# Schematic.net
KiCad netlist of a schematic drawn in EAGLE
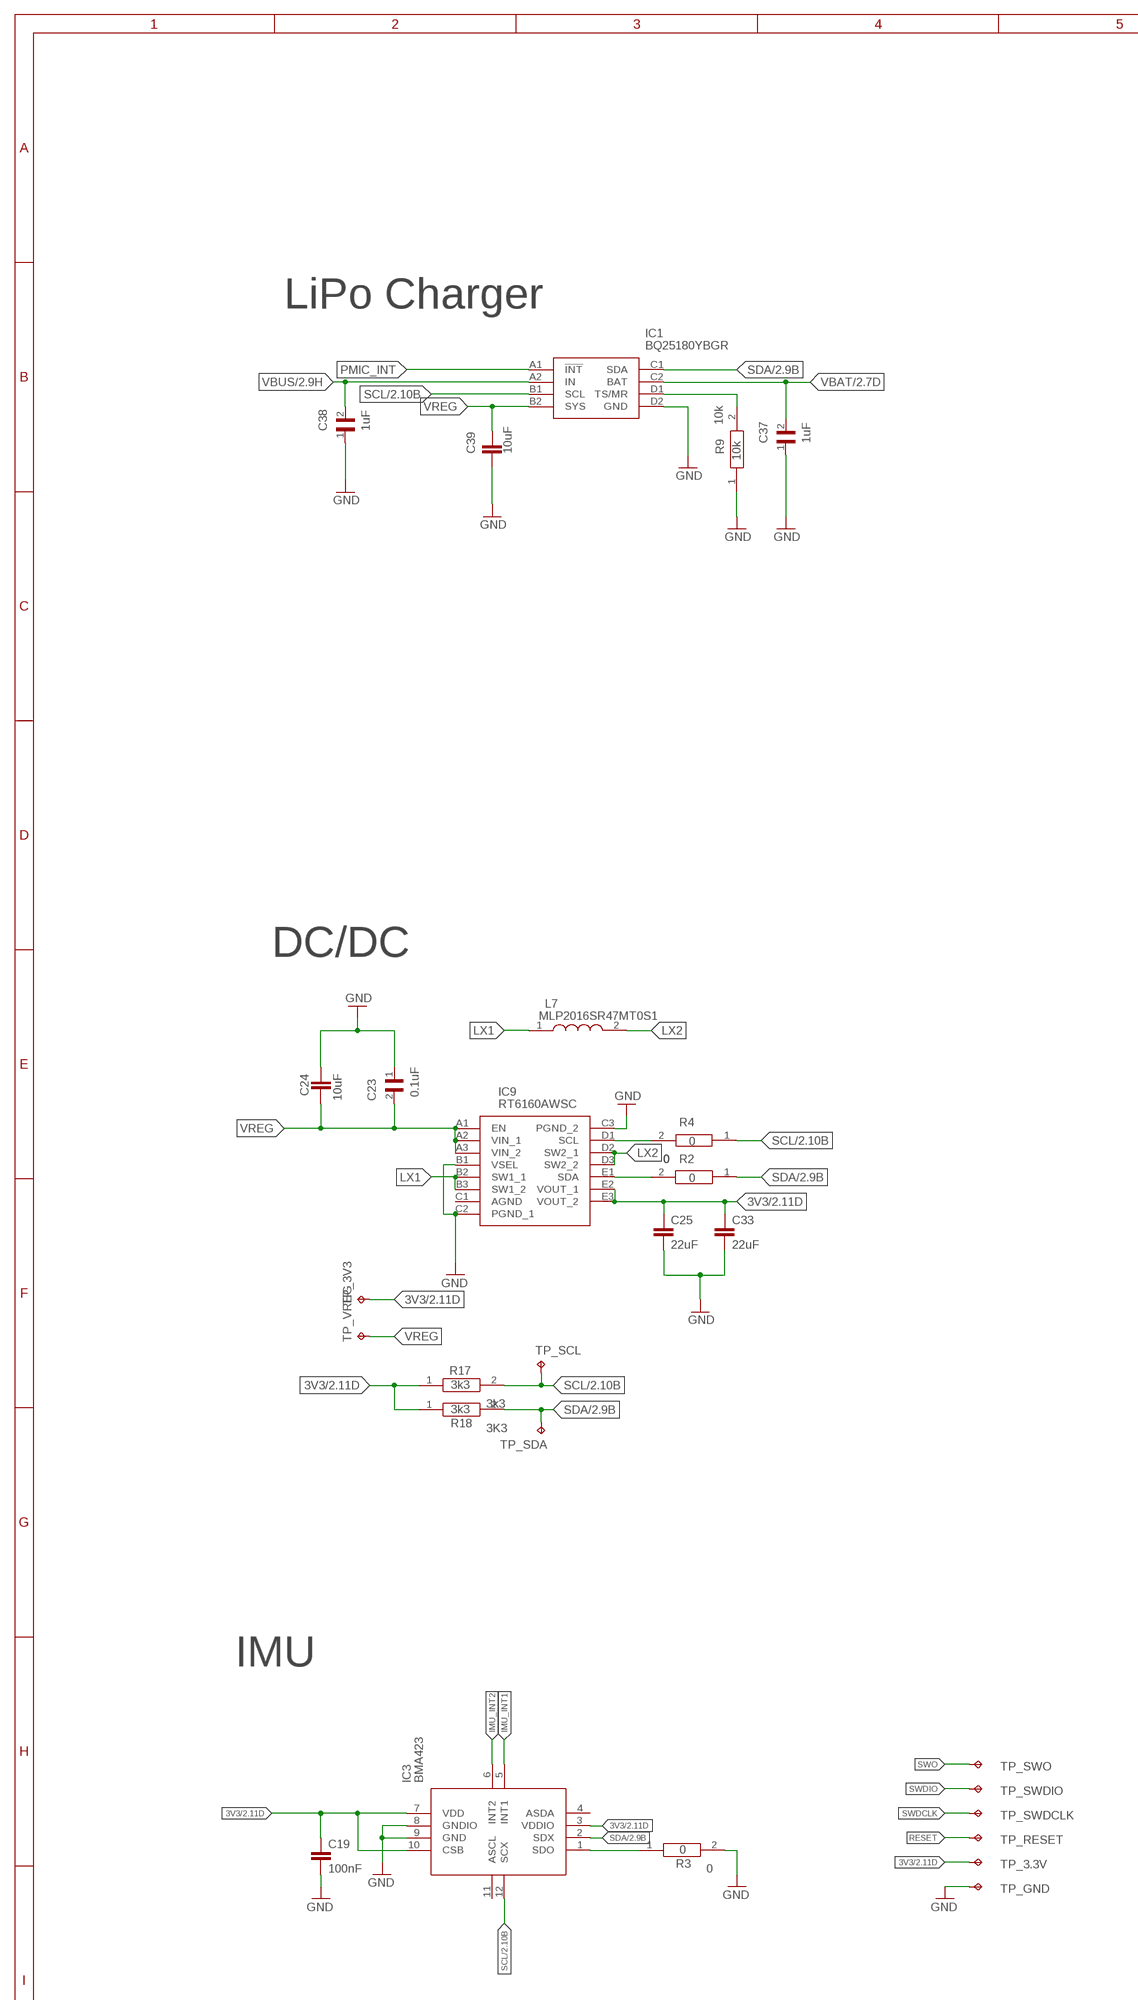
[diagram p0: schematic, sheet 1, part 1 of 2]
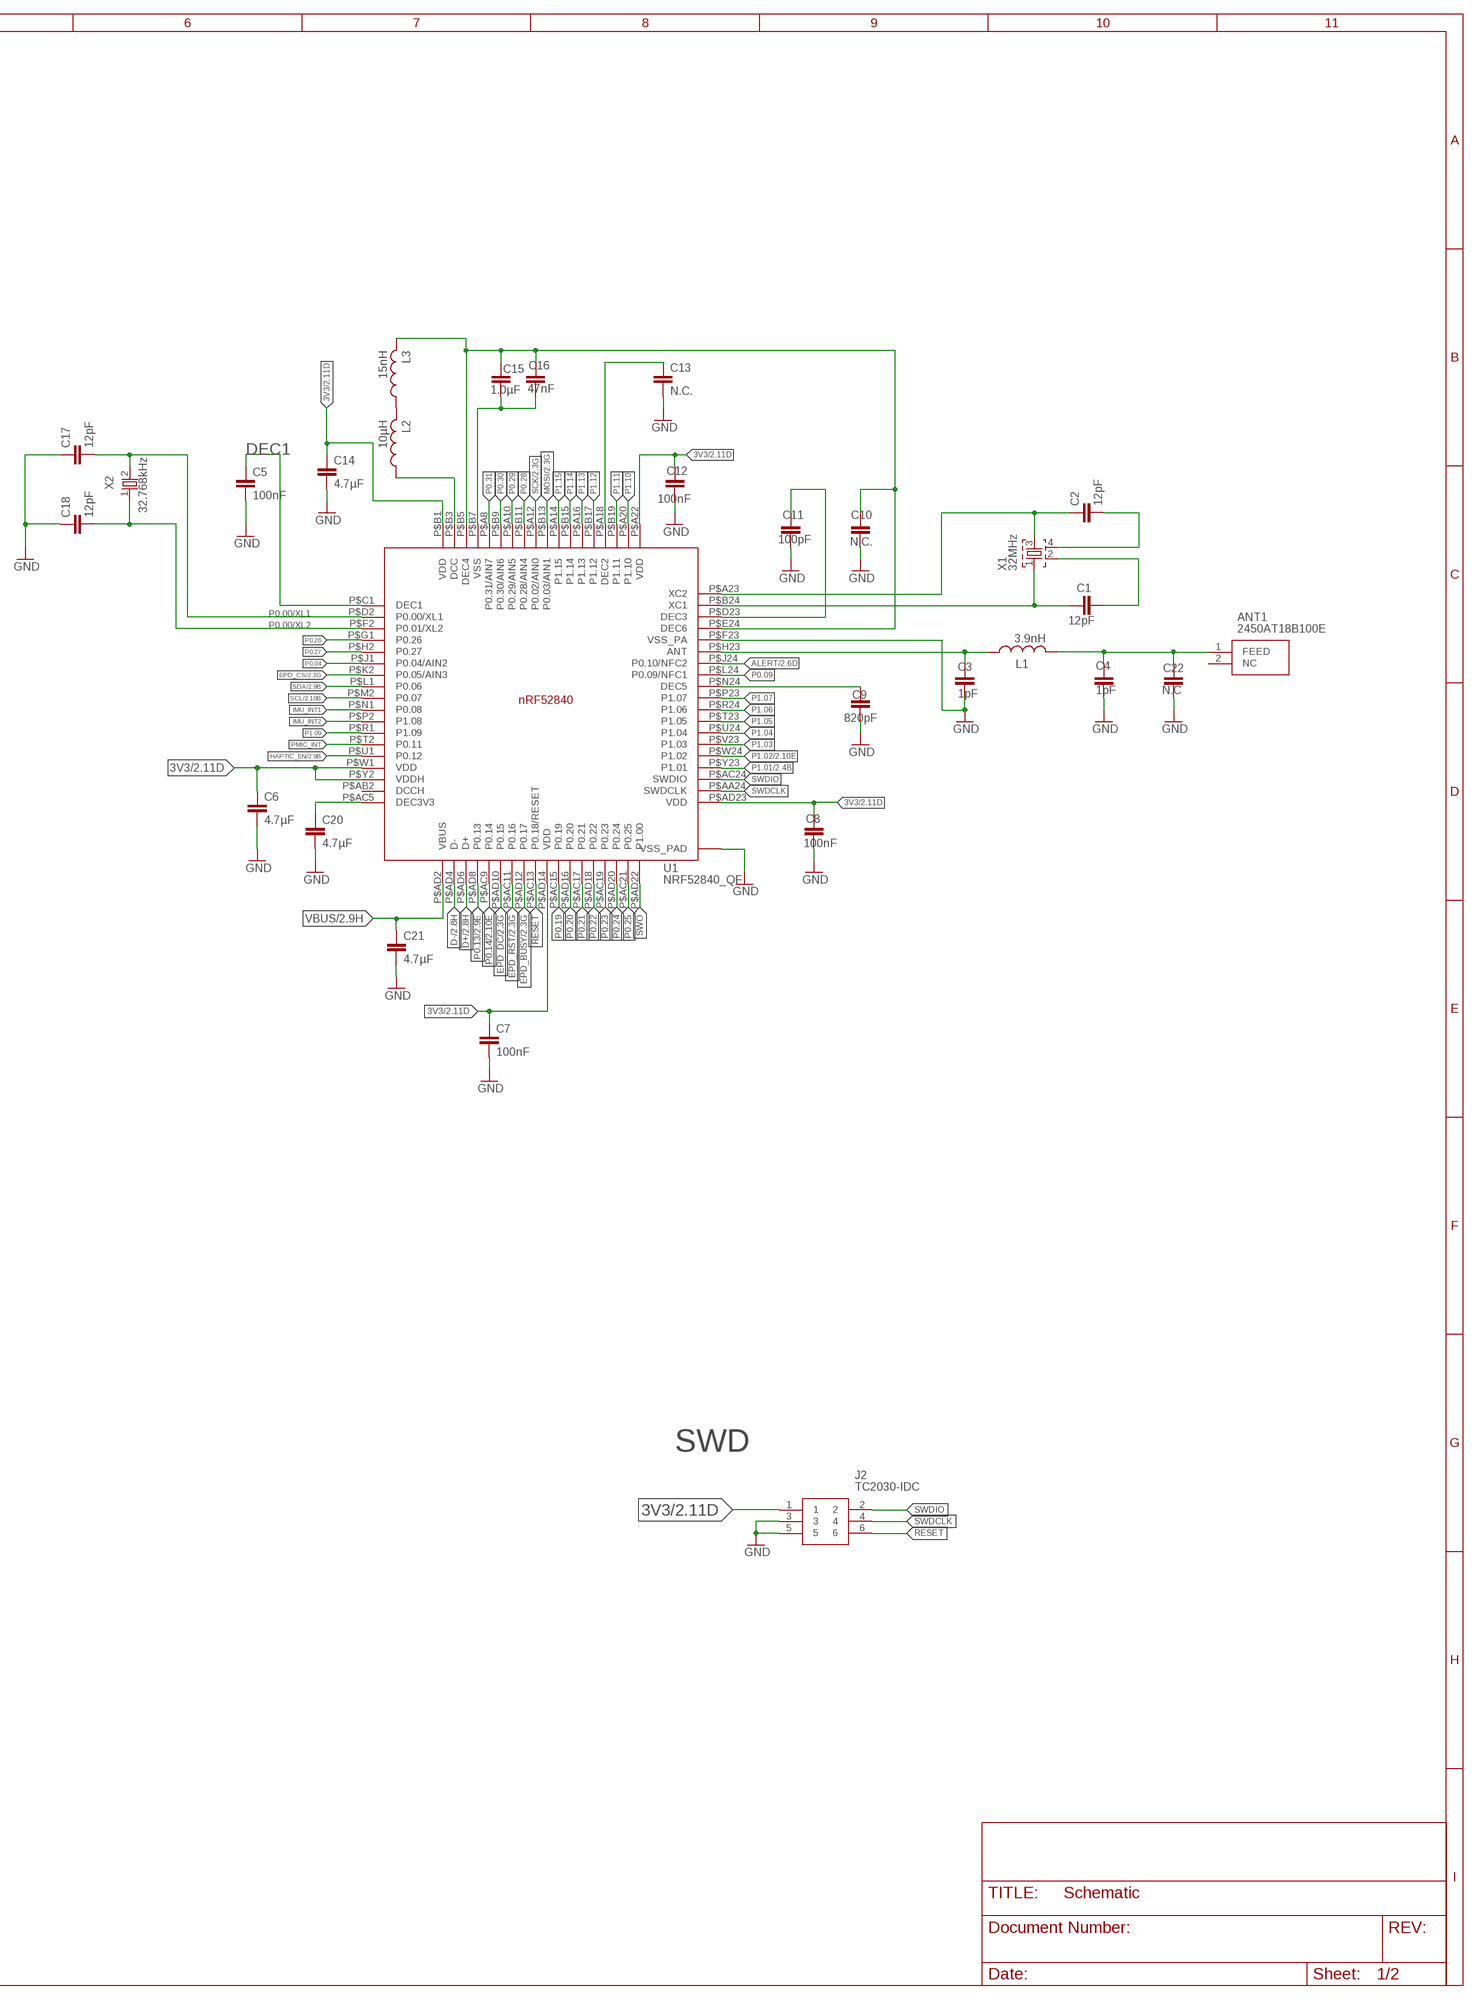
[diagram p1: schematic, sheet 1, part 2 of 2]
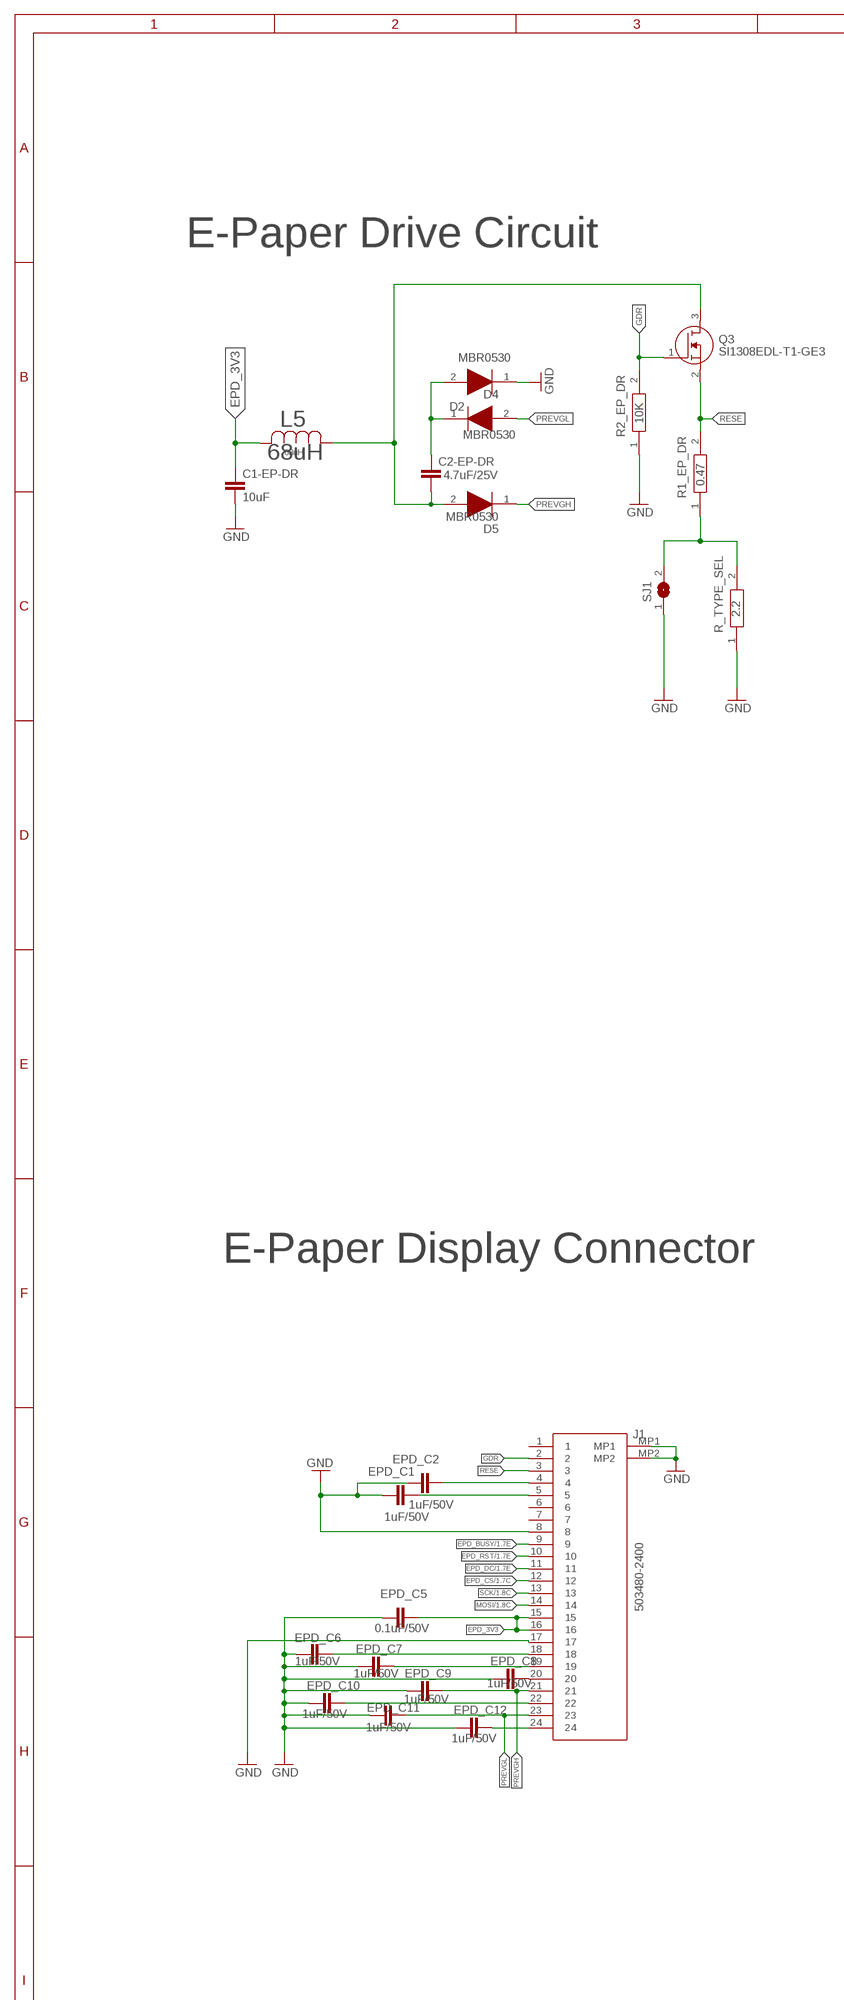
[diagram p2: schematic, sheet 2, part 1 of 2]
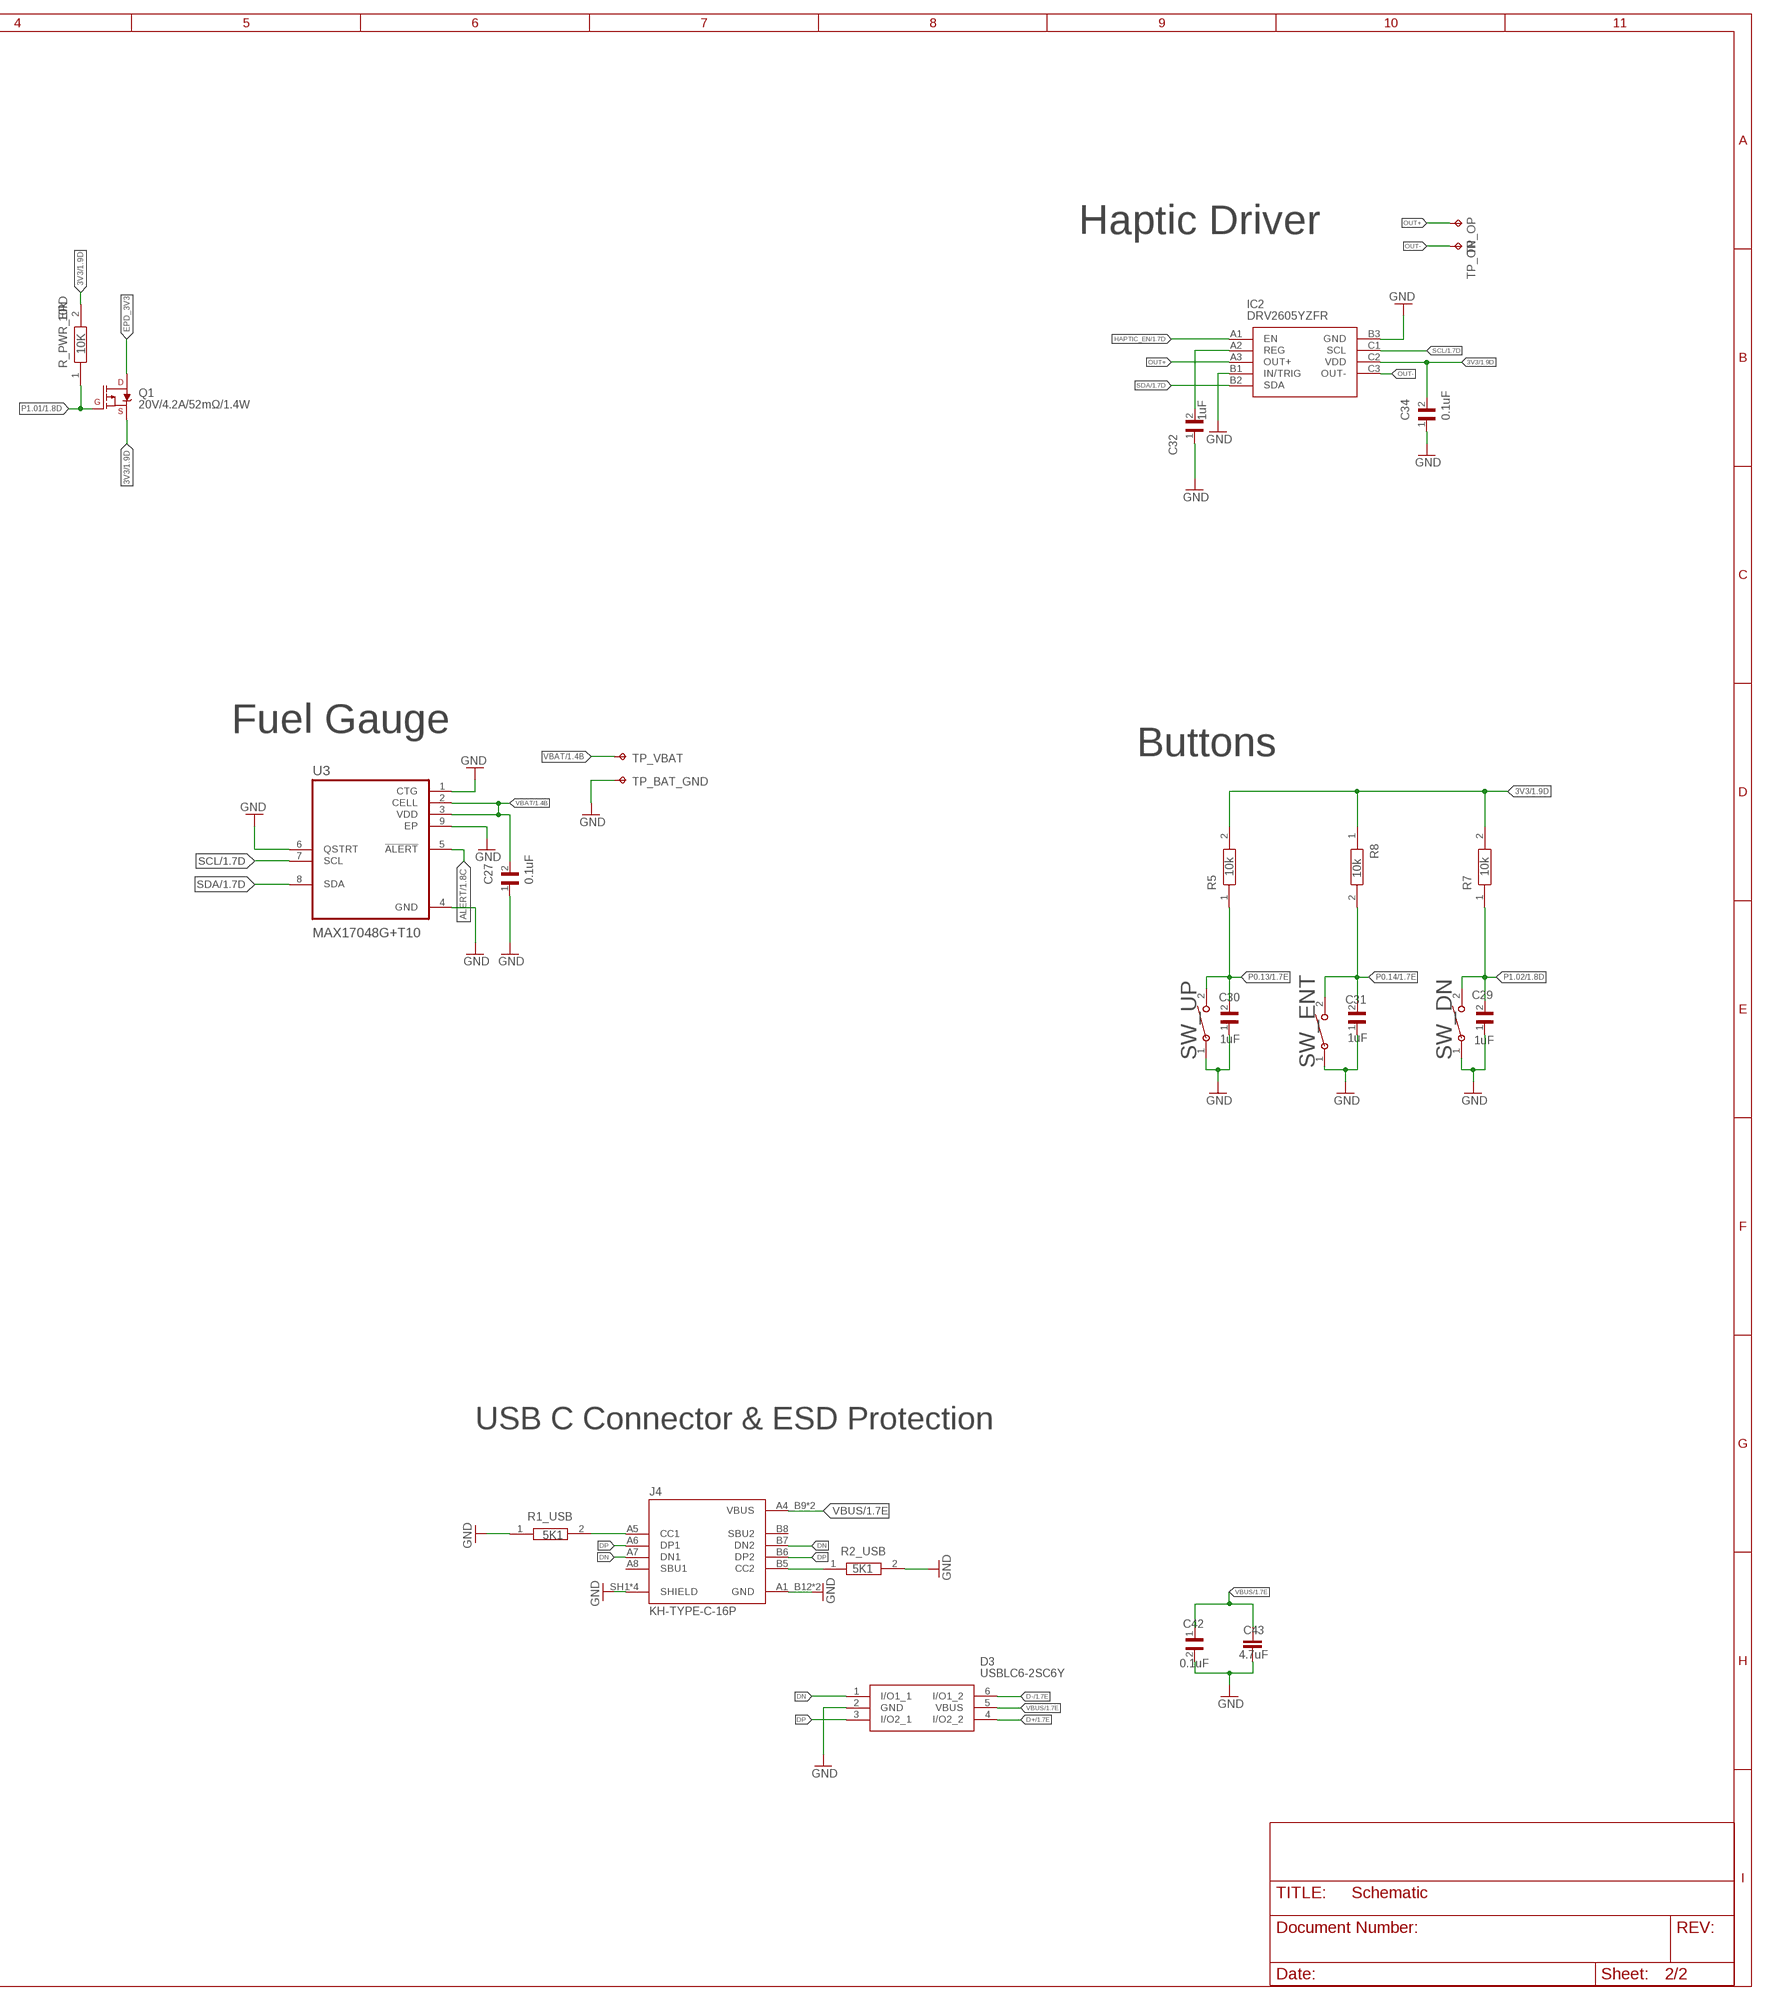
[diagram p3: schematic, sheet 2, part 2 of 2]

(export (version "E")
  (design (tool "Eeschema 10.0.6"))
  (components
    (comp (ref "C1-EP-DR")
      (value "10uF")
      (footprint "eagle-import:NORDIC_NRF_3_RESC0402_L")
      (libsource (lib "eagle-import") (part "InkTime_v5_vf.tUwrbmbJTRevvyDZ4HcNKA_NORDIC_NRF_3_CAPACITOR_0402_L"))
    )
    (comp (ref "C2-EP-DR")
      (value "4.7uF/25V")
      (footprint "eagle-import:NORDIC_NRF_3_RESC0402_L")
      (libsource (lib "eagle-import") (part "InkTime_v5_vf.tUwrbmbJTRevvyDZ4HcNKA_NORDIC_NRF_3_CAPACITOR_0402_L"))
    )
    (comp (ref "C27")
      (value "0.1uF")
      (footprint "eagle-import:GRM011R60J152KE01L_2_CAPC0201X13N")
      (fields (field (name "MF") "Murata") (field (name "MP") "GRM011R60J152KE01L"))
      (libsource (lib "eagle-import") (part "GRM011R60J152KE01L_2_GRM011R60J152KE01L"))
    )
    (comp (ref "C29")
      (value "1uF")
      (footprint "eagle-import:GRM011R60J152KE01L_2_CAPC0201X13N")
      (fields (field (name "MF") "Murata") (field (name "MP") "GRM011R60J152KE01L"))
      (libsource (lib "eagle-import") (part "GRM011R60J152KE01L_2_GRM011R60J152KE01L"))
    )
    (comp (ref "C30")
      (value "1uF")
      (footprint "eagle-import:GRM011R60J152KE01L_2_CAPC0201X13N")
      (fields (field (name "MF") "Murata") (field (name "MP") "GRM011R60J152KE01L"))
      (libsource (lib "eagle-import") (part "GRM011R60J152KE01L_2_GRM011R60J152KE01L"))
    )
    (comp (ref "C31")
      (value "1uF")
      (footprint "eagle-import:GRM011R60J152KE01L_2_CAPC0201X13N")
      (fields (field (name "MF") "Murata") (field (name "MP") "GRM011R60J152KE01L"))
      (libsource (lib "eagle-import") (part "GRM011R60J152KE01L_2_GRM011R60J152KE01L"))
    )
    (comp (ref "C32")
      (value "1uF")
      (footprint "eagle-import:GRM011R60J152KE01L_2_CAPC0201X13N")
      (fields (field (name "MF") "Murata") (field (name "MP") "GRM011R60J152KE01L"))
      (libsource (lib "eagle-import") (part "GRM011R60J152KE01L_2_GRM011R60J152KE01L"))
    )
    (comp (ref "C34")
      (value "0.1uF")
      (footprint "eagle-import:GRM011R60J152KE01L_2_CAPC0201X13N")
      (fields (field (name "MF") "Murata") (field (name "MP") "GRM011R60J152KE01L"))
      (libsource (lib "eagle-import") (part "GRM011R60J152KE01L_2_GRM011R60J152KE01L"))
    )
    (comp (ref "C42")
      (value "0.1uF")
      (footprint "eagle-import:GRM011R60J152KE01L_2_CAPC0201X13N")
      (fields (field (name "MF") "Murata") (field (name "MP") "GRM011R60J152KE01L"))
      (libsource (lib "eagle-import") (part "GRM011R60J152KE01L_2_GRM011R60J152KE01L"))
    )
    (comp (ref "C43")
      (value "4.7uF")
      (footprint "eagle-import:NORDIC_NRF_3_RESC0402_L")
      (libsource (lib "eagle-import") (part "InkTime_v5_vf.tUwrbmbJTRevvyDZ4HcNKA_NORDIC_NRF_3_CAPACITOR_0402_L"))
    )
    (comp (ref "D2")
      (value "MBR0530")
      (footprint "eagle-import:ESP32_C6_LIBRARY_5_SOD3716X135N")
      (fields (field (name "MF") "ON Semiconductor"))
      (libsource (lib "eagle-import") (part "ESP32_C6_LIBRARY_5_MBR0530"))
    )
    (comp (ref "D3")
      (value "USBLC6-2SC6Y")
      (footprint "eagle-import:ESP32_C6_LIBRARY_3_SOT95P280X145-6N")
      (fields (field (name "MF") "STMicroelectronics"))
      (libsource (lib "eagle-import") (part "ESP32_C6_LIBRARY_3_USBLC6-2SC6Y"))
    )
    (comp (ref "D4")
      (value "MBR0530")
      (footprint "eagle-import:ESP32_C6_LIBRARY_5_SOD3716X135N")
      (fields (field (name "MF") "ON Semiconductor"))
      (libsource (lib "eagle-import") (part "ESP32_C6_LIBRARY_5_MBR0530"))
    )
    (comp (ref "D5")
      (value "MBR0530")
      (footprint "eagle-import:ESP32_C6_LIBRARY_5_SOD3716X135N")
      (fields (field (name "MF") "ON Semiconductor"))
      (libsource (lib "eagle-import") (part "ESP32_C6_LIBRARY_5_MBR0530"))
    )
    (comp (ref "EPD_C1")
      (value "1uF/50V")
      (footprint "eagle-import:NORDIC_NRF_3_RESC0402_L")
      (libsource (lib "eagle-import") (part "InkTime_v5_vf.tUwrbmbJTRevvyDZ4HcNKA_NORDIC_NRF_3_CAPACITOR_0402_L"))
    )
    (comp (ref "EPD_C2")
      (value "1uF/50V")
      (footprint "eagle-import:NORDIC_NRF_3_RESC0402_L")
      (libsource (lib "eagle-import") (part "InkTime_v5_vf.tUwrbmbJTRevvyDZ4HcNKA_NORDIC_NRF_3_CAPACITOR_0402_L"))
    )
    (comp (ref "EPD_C5")
      (value "0.1uF/50V")
      (footprint "eagle-import:NORDIC_NRF_3_RESC0402_L")
      (libsource (lib "eagle-import") (part "InkTime_v5_vf.tUwrbmbJTRevvyDZ4HcNKA_NORDIC_NRF_3_CAPACITOR_0402_L"))
    )
    (comp (ref "EPD_C6")
      (value "1uF/50V")
      (footprint "eagle-import:NORDIC_NRF_3_RESC0402_L")
      (libsource (lib "eagle-import") (part "InkTime_v5_vf.tUwrbmbJTRevvyDZ4HcNKA_NORDIC_NRF_3_CAPACITOR_0402_L"))
    )
    (comp (ref "EPD_C7")
      (value "1uF/50V")
      (footprint "eagle-import:NORDIC_NRF_3_RESC0402_L")
      (libsource (lib "eagle-import") (part "InkTime_v5_vf.tUwrbmbJTRevvyDZ4HcNKA_NORDIC_NRF_3_CAPACITOR_0402_L"))
    )
    (comp (ref "EPD_C8")
      (value "1uF/50V")
      (footprint "eagle-import:NORDIC_NRF_3_RESC0402_L")
      (libsource (lib "eagle-import") (part "InkTime_v5_vf.tUwrbmbJTRevvyDZ4HcNKA_NORDIC_NRF_3_CAPACITOR_0402_L"))
    )
    (comp (ref "EPD_C9")
      (value "1uF/50V")
      (footprint "eagle-import:NORDIC_NRF_3_RESC0402_L")
      (libsource (lib "eagle-import") (part "InkTime_v5_vf.tUwrbmbJTRevvyDZ4HcNKA_NORDIC_NRF_3_CAPACITOR_0402_L"))
    )
    (comp (ref "EPD_C10")
      (value "1uF/50V")
      (footprint "eagle-import:NORDIC_NRF_3_RESC0402_L")
      (libsource (lib "eagle-import") (part "InkTime_v5_vf.tUwrbmbJTRevvyDZ4HcNKA_NORDIC_NRF_3_CAPACITOR_0402_L"))
    )
    (comp (ref "EPD_C11")
      (value "1uF/50V")
      (footprint "eagle-import:NORDIC_NRF_3_RESC0402_L")
      (libsource (lib "eagle-import") (part "InkTime_v5_vf.tUwrbmbJTRevvyDZ4HcNKA_NORDIC_NRF_3_CAPACITOR_0402_L"))
    )
    (comp (ref "EPD_C12")
      (value "1uF/50V")
      (footprint "eagle-import:NORDIC_NRF_3_RESC0402_L")
      (libsource (lib "eagle-import") (part "InkTime_v5_vf.tUwrbmbJTRevvyDZ4HcNKA_NORDIC_NRF_3_CAPACITOR_0402_L"))
    )
    (comp (ref "IC2")
      (value "DRV2605YZFR")
      (footprint "eagle-import:DRV2605YZFR_BGA9C50P3X3_144X144X62")
      (libsource (lib "eagle-import") (part "DRV2605YZFR_DRV2605YZFR"))
    )
    (comp (ref "J1")
      (value "503480-2400")
      (footprint "eagle-import:503480-2400_5034802400")
      (fields (field (name "MOUSER_PART_NUMBER") "538-503480-2400"))
      (libsource (lib "eagle-import") (part "503480-2400_503480-2400"))
    )
    (comp (ref "J4")
      (value "KH-TYPE-C-16P")
      (footprint "eagle-import:KH-TYPE-C-16P_KINGHELM_KH-TYPE-C-16P")
      (fields (field (name "MF") "kinghelm"))
      (libsource (lib "eagle-import") (part "KH-TYPE-C-16P_KH-TYPE-C-16P"))
    )
    (comp (ref "L5")
      (value "68uH")
      (footprint "eagle-import:ESP32_C6_LIBRARY_2_IND_4828-WE-TPC_WRE")
      (fields
        (field (name "MANUFACTURER_PART_NUMBER") "744043680")
        (field (name "SHOW_VALUE") "68uH")
        (field (name "COPYRIGHT") "Copyright (C) 2024 Ultra Librarian. All rights reserved.")
      )
      (libsource (lib "eagle-import") (part "ESP32_C6_LIBRARY_2_744043680IND_4828-WE-TPC_WRE"))
    )
    (comp (ref "Q1")
      (value "20V/4.2A/52mΩ/1.4W")
      (footprint "eagle-import:ESP32_C6_LIBRARY_4_ESP32_C6_LIBRARY_4_ESP32_C6_LIBRARY_4_ESP32_C6_LIBRARY_4_ESP32_WROVER_SPARKFUN-DISCRETESEMI_SOT23-3")
      (libsource (lib "eagle-import") (part "ESP32_C6_LIBRARY_4_ESP32_WROVER_SPARKFUN-DISCRETESEMI_MOSFET_PCH-DMG2305UX-7"))
    )
    (comp (ref "Q3")
      (value "SI1308EDL-T1-GE3")
      (footprint "eagle-import:ESP32_C6_LIBRARY_6_SOT65P210X110-3N")
      (fields (field (name "MF") "Vishay Siliconix"))
      (libsource (lib "eagle-import") (part "ESP32_C6_LIBRARY_6_SI1308EDL-T1-GE3"))
    )
    (comp (ref "R1_EP_DR")
      (value "0.47")
      (footprint "eagle-import:ERA-1AEB3401C_0201")
      (libsource (lib "eagle-import") (part "ERA-1AEB3401C_CPF0201D7K68C1"))
    )
    (comp (ref "R1_USB")
      (value "5K1")
      (footprint "eagle-import:ERA-1AEB3401C_0201")
      (libsource (lib "eagle-import") (part "ERA-1AEB3401C_CPF0201D7K68C1"))
    )
    (comp (ref "R2_EP_DR")
      (value "10K")
      (footprint "eagle-import:ERA-1AEB3401C_0201")
      (libsource (lib "eagle-import") (part "ERA-1AEB3401C_CPF0201D7K68C1"))
    )
    (comp (ref "R2_USB")
      (value "5K1")
      (footprint "eagle-import:ERA-1AEB3401C_0201")
      (libsource (lib "eagle-import") (part "ERA-1AEB3401C_CPF0201D7K68C1"))
    )
    (comp (ref "R5")
      (value "10k")
      (footprint "eagle-import:ERA-1AEB3401C_0201")
      (libsource (lib "eagle-import") (part "ERA-1AEB3401C_CPF0201D7K68C1"))
    )
    (comp (ref "R7")
      (value "10k")
      (footprint "eagle-import:ERA-1AEB3401C_0201")
      (libsource (lib "eagle-import") (part "ERA-1AEB3401C_CPF0201D7K68C1"))
    )
    (comp (ref "R8")
      (value "10k")
      (footprint "eagle-import:ERA-1AEB3401C_0201")
      (libsource (lib "eagle-import") (part "ERA-1AEB3401C_CPF0201D7K68C1"))
    )
    (comp (ref "R_PWR_EPD")
      (value "10k")
      (footprint "eagle-import:ERA-1AEB3401C_0201")
      (fields (field (name "RESISTANCE") "10K"))
      (libsource (lib "eagle-import") (part "ERA-1AEB3401C_CPF0201D7K68C1"))
    )
    (comp (ref "R_TYPE_SEL")
      (value "2.2")
      (footprint "eagle-import:ERA-1AEB3401C_0201")
      (libsource (lib "eagle-import") (part "ERA-1AEB3401C_CPF0201D7K68C1"))
    )
    (comp (ref "SJ1")
      (value "ESP32_C6_LIBRARY_7_JUMPER_SJ")
      (footprint "eagle-import:ESP32_C6_LIBRARY_7_JUMPER_SJ")
      (libsource (lib "eagle-import") (part "ESP32_C6_LIBRARY_7_JUMPER_SJ"))
    )
    (comp (ref "SW_DN")
      (value "2025-10-22_07-23-44_LIBRARY_EVP-AKE31ASW_EVP-AKE31A_PAN")
      (footprint "eagle-import:2025-10-22_07-23-44_LIBRARY_SW_EVP-AKE31A_PAN")
      (fields
        (field (name "MANUFACTURER_PART_NUMBER") "EVP-AKE31A")
        (field (name "COPYRIGHT") "Copyright (C) 2025 Ultra Librarian. All rights reserved.")
      )
      (libsource (lib "eagle-import") (part "2025-10-22_07-23-44_LIBRARY_EVP-AKE31ASW_EVP-AKE31A_PAN"))
    )
    (comp (ref "SW_ENT")
      (value "2025-10-22_07-23-44_LIBRARY_EVP-AKE31ASW_EVP-AKE31A_PAN")
      (footprint "eagle-import:2025-10-22_07-23-44_LIBRARY_SW_EVP-AKE31A_PAN")
      (fields
        (field (name "MANUFACTURER_PART_NUMBER") "EVP-AKE31A")
        (field (name "COPYRIGHT") "Copyright (C) 2025 Ultra Librarian. All rights reserved.")
      )
      (libsource (lib "eagle-import") (part "2025-10-22_07-23-44_LIBRARY_EVP-AKE31ASW_EVP-AKE31A_PAN"))
    )
    (comp (ref "SW_UP")
      (value "2025-10-22_07-23-44_LIBRARY_EVP-AKE31ASW_EVP-AKE31A_PAN")
      (footprint "eagle-import:2025-10-22_07-23-44_LIBRARY_SW_EVP-AKE31A_PAN")
      (fields
        (field (name "MANUFACTURER_PART_NUMBER") "EVP-AKE31A")
        (field (name "COPYRIGHT") "Copyright (C) 2025 Ultra Librarian. All rights reserved.")
      )
      (libsource (lib "eagle-import") (part "2025-10-22_07-23-44_LIBRARY_EVP-AKE31ASW_EVP-AKE31A_PAN"))
    )
    (comp (ref "TP_BAT_GND")
      (value "HECTOR_WATCH_1_TPTP20R")
      (footprint "eagle-import:HECTOR_WATCH_1_TP20R")
      (libsource (lib "eagle-import") (part "HECTOR_WATCH_1_TPTP20R"))
    )
    (comp (ref "TP_ON")
      (value "HECTOR_WATCH_1_TPTP20R")
      (footprint "eagle-import:HECTOR_WATCH_1_TP20R")
      (libsource (lib "eagle-import") (part "HECTOR_WATCH_1_TPTP20R"))
    )
    (comp (ref "TP_OP")
      (value "HECTOR_WATCH_1_TPTP20R")
      (footprint "eagle-import:HECTOR_WATCH_1_TP20R")
      (libsource (lib "eagle-import") (part "HECTOR_WATCH_1_TPTP20R"))
    )
    (comp (ref "TP_VBAT")
      (value "HECTOR_WATCH_1_TPTP20R")
      (footprint "eagle-import:HECTOR_WATCH_1_TP20R")
      (libsource (lib "eagle-import") (part "HECTOR_WATCH_1_TPTP20R"))
    )
    (comp (ref "U3")
      (value "MAX17048G+T10")
      (footprint "eagle-import:ESP32_C6_LIBRARY_SON50P200X200X80-9N")
      (fields (field (name "MF") "Analog Devices"))
      (libsource (lib "eagle-import") (part "ESP32_C6_LIBRARY_MAX17048G+T10"))
    )
    (comp (ref "ANT1")
      (value "2450AT18B100E")
      (footprint "eagle-import:2450AT18B100E_ANTC3216X140N")
      (fields (field (name "MOUSER_PART_NUMBER") "609-2450AT18B100E"))
      (libsource (lib "eagle-import") (part "2450AT18B100E_2450AT18B100E"))
    )
    (comp (ref "C1")
      (value "12pF")
      (footprint "eagle-import:NORDIC_NRF_3_RESC0201_L")
      (libsource (lib "eagle-import") (part "InkTime_v5_vf.tUwrbmbJTRevvyDZ4HcNKA_NORDIC_NRF_3_CAPACITOR_0201_L"))
    )
    (comp (ref "C2")
      (value "12pF")
      (footprint "eagle-import:NORDIC_NRF_3_RESC0201_L")
      (libsource (lib "eagle-import") (part "InkTime_v5_vf.tUwrbmbJTRevvyDZ4HcNKA_NORDIC_NRF_3_CAPACITOR_0201_L"))
    )
    (comp (ref "C3")
      (value "1pF")
      (footprint "eagle-import:NORDIC_NRF_3_RESC0201_L")
      (libsource (lib "eagle-import") (part "InkTime_v5_vf.tUwrbmbJTRevvyDZ4HcNKA_NORDIC_NRF_3_CAPACITOR_0201_L"))
    )
    (comp (ref "C4")
      (value "1pF")
      (footprint "eagle-import:NORDIC_NRF_3_RESC0201_L")
      (libsource (lib "eagle-import") (part "InkTime_v5_vf.tUwrbmbJTRevvyDZ4HcNKA_NORDIC_NRF_3_CAPACITOR_0201_L"))
    )
    (comp (ref "C5")
      (value "100nF")
      (footprint "eagle-import:NORDIC_NRF_3_RESC0201_L")
      (libsource (lib "eagle-import") (part "InkTime_v5_vf.tUwrbmbJTRevvyDZ4HcNKA_NORDIC_NRF_3_CAPACITOR_0201_L"))
    )
    (comp (ref "C6")
      (value "4.7µF")
      (footprint "eagle-import:NORDIC_NRF_3_RESC0201_L")
      (libsource (lib "eagle-import") (part "InkTime_v5_vf.tUwrbmbJTRevvyDZ4HcNKA_NORDIC_NRF_3_CAPACITOR_0201_L"))
    )
    (comp (ref "C7")
      (value "100nF")
      (footprint "eagle-import:NORDIC_NRF_3_RESC0201_L")
      (libsource (lib "eagle-import") (part "InkTime_v5_vf.tUwrbmbJTRevvyDZ4HcNKA_NORDIC_NRF_3_CAPACITOR_0201_L"))
    )
    (comp (ref "C8")
      (value "100nF")
      (footprint "eagle-import:NORDIC_NRF_3_RESC0201_L")
      (libsource (lib "eagle-import") (part "InkTime_v5_vf.tUwrbmbJTRevvyDZ4HcNKA_NORDIC_NRF_3_CAPACITOR_0201_L"))
    )
    (comp (ref "C9")
      (value "820pF")
      (footprint "eagle-import:NORDIC_NRF_3_RESC0201_L")
      (libsource (lib "eagle-import") (part "InkTime_v5_vf.tUwrbmbJTRevvyDZ4HcNKA_NORDIC_NRF_3_CAPACITOR_0201_L"))
    )
    (comp (ref "C10")
      (value "N.C.")
      (footprint "eagle-import:NORDIC_NRF_3_RESC0201_L")
      (libsource (lib "eagle-import") (part "InkTime_v5_vf.tUwrbmbJTRevvyDZ4HcNKA_NORDIC_NRF_3_CAPACITOR_0201_L"))
    )
    (comp (ref "C11")
      (value "100pF")
      (footprint "eagle-import:NORDIC_NRF_3_RESC0201_L")
      (libsource (lib "eagle-import") (part "InkTime_v5_vf.tUwrbmbJTRevvyDZ4HcNKA_NORDIC_NRF_3_CAPACITOR_0201_L"))
    )
    (comp (ref "C12")
      (value "100nF")
      (footprint "eagle-import:NORDIC_NRF_3_RESC0201_L")
      (libsource (lib "eagle-import") (part "InkTime_v5_vf.tUwrbmbJTRevvyDZ4HcNKA_NORDIC_NRF_3_CAPACITOR_0201_L"))
    )
    (comp (ref "C13")
      (value "N.C.")
      (footprint "eagle-import:NORDIC_NRF_3_RESC0201_L")
      (libsource (lib "eagle-import") (part "InkTime_v5_vf.tUwrbmbJTRevvyDZ4HcNKA_NORDIC_NRF_3_CAPACITOR_0201_L"))
    )
    (comp (ref "C14")
      (value "4.7µF")
      (footprint "eagle-import:NORDIC_NRF_3_RESC0201_L")
      (libsource (lib "eagle-import") (part "InkTime_v5_vf.tUwrbmbJTRevvyDZ4HcNKA_NORDIC_NRF_3_CAPACITOR_0201_L"))
    )
    (comp (ref "C15")
      (value "1.0µF")
      (footprint "eagle-import:NORDIC_NRF_3_RESC0201_L")
      (libsource (lib "eagle-import") (part "InkTime_v5_vf.tUwrbmbJTRevvyDZ4HcNKA_NORDIC_NRF_3_CAPACITOR_0201_L"))
    )
    (comp (ref "C16")
      (value "47nF")
      (footprint "eagle-import:NORDIC_NRF_3_RESC0201_L")
      (libsource (lib "eagle-import") (part "InkTime_v5_vf.tUwrbmbJTRevvyDZ4HcNKA_NORDIC_NRF_3_CAPACITOR_0201_L"))
    )
    (comp (ref "C17")
      (value "12pF")
      (footprint "eagle-import:NORDIC_NRF_3_RESC0201_L")
      (libsource (lib "eagle-import") (part "InkTime_v5_vf.tUwrbmbJTRevvyDZ4HcNKA_NORDIC_NRF_3_CAPACITOR_0201_L"))
    )
    (comp (ref "C18")
      (value "12pF")
      (footprint "eagle-import:NORDIC_NRF_3_RESC0201_L")
      (libsource (lib "eagle-import") (part "InkTime_v5_vf.tUwrbmbJTRevvyDZ4HcNKA_NORDIC_NRF_3_CAPACITOR_0201_L"))
    )
    (comp (ref "C19")
      (value "100nF")
      (footprint "eagle-import:NORDIC_NRF_3_RESC0402_L")
      (libsource (lib "eagle-import") (part "InkTime_v5_vf.tUwrbmbJTRevvyDZ4HcNKA_NORDIC_NRF_3_CAPACITOR_0402_L"))
    )
    (comp (ref "C20")
      (value "4.7µF")
      (footprint "eagle-import:NORDIC_NRF_3_RESC0201_L")
      (libsource (lib "eagle-import") (part "InkTime_v5_vf.tUwrbmbJTRevvyDZ4HcNKA_NORDIC_NRF_3_CAPACITOR_0201_L"))
    )
    (comp (ref "C21")
      (value "4.7µF")
      (footprint "eagle-import:NORDIC_NRF_3_RESC0201_L")
      (libsource (lib "eagle-import") (part "InkTime_v5_vf.tUwrbmbJTRevvyDZ4HcNKA_NORDIC_NRF_3_CAPACITOR_0201_L"))
    )
    (comp (ref "C22")
      (value "N.C")
      (footprint "eagle-import:NORDIC_NRF_3_RESC0201_L")
      (libsource (lib "eagle-import") (part "InkTime_v5_vf.tUwrbmbJTRevvyDZ4HcNKA_NORDIC_NRF_3_CAPACITOR_0201_L"))
    )
    (comp (ref "C23")
      (value "0.1uF")
      (footprint "eagle-import:GRM011R60J152KE01L_2_CAPC0201X13N")
      (fields (field (name "MF") "Murata") (field (name "MP") "GRM011R60J152KE01L"))
      (libsource (lib "eagle-import") (part "GRM011R60J152KE01L_2_GRM011R60J152KE01L"))
    )
    (comp (ref "C24")
      (value "10uF")
      (footprint "eagle-import:NORDIC_NRF_3_RESC0402_L")
      (libsource (lib "eagle-import") (part "InkTime_v5_vf.tUwrbmbJTRevvyDZ4HcNKA_NORDIC_NRF_3_CAPACITOR_0402_L"))
    )
    (comp (ref "C25")
      (value "22uF")
      (footprint "eagle-import:NORDIC_NRF_3_RESC0201_L")
      (libsource (lib "eagle-import") (part "NORDIC_NRF_3_CAPACITOR_0201_L"))
    )
    (comp (ref "C33")
      (value "22uF")
      (footprint "eagle-import:NORDIC_NRF_3_RESC0402_L")
      (libsource (lib "eagle-import") (part "InkTime_v5_vf.tUwrbmbJTRevvyDZ4HcNKA_NORDIC_NRF_3_CAPACITOR_0402_L"))
    )
    (comp (ref "C37")
      (value "1uF")
      (footprint "eagle-import:GRM011R60J152KE01L_2_CAPC0201X13N")
      (fields (field (name "MF") "Murata") (field (name "MP") "GRM011R60J152KE01L"))
      (libsource (lib "eagle-import") (part "GRM011R60J152KE01L_2_GRM011R60J152KE01L"))
    )
    (comp (ref "C38")
      (value "1uF")
      (footprint "eagle-import:GRM011R60J152KE01L_2_CAPC0201X13N")
      (fields (field (name "MF") "Murata") (field (name "MP") "GRM011R60J152KE01L"))
      (libsource (lib "eagle-import") (part "GRM011R60J152KE01L_2_GRM011R60J152KE01L"))
    )
    (comp (ref "C39")
      (value "10uF")
      (footprint "eagle-import:NORDIC_NRF_3_RESC0402_L")
      (libsource (lib "eagle-import") (part "InkTime_v5_vf.tUwrbmbJTRevvyDZ4HcNKA_NORDIC_NRF_3_CAPACITOR_0402_L"))
    )
    (comp (ref "IC1")
      (value "BQ25180YBGR")
      (footprint "eagle-import:BQ25180YBGR_BGA8C40P2X4_100X155X50")
      (fields (field (name "MOUSER_PART_NUMBER") "595-BQ25180YBGR"))
      (libsource (lib "eagle-import") (part "BQ25180YBGR_BQ25180YBGR"))
    )
    (comp (ref "IC3")
      (value "BMA423")
      (footprint "eagle-import:BMA423_BMA423")
      (fields (field (name "MOUSER_PART_NUMBER") "262-BMA423"))
      (libsource (lib "eagle-import") (part "BMA423_BMA423"))
    )
    (comp (ref "IC9")
      (value "RT6160AWSC")
      (footprint "eagle-import:RT6160AWSC_BGA15C40P3X5_140X230X60")
      (fields (field (name "MOUSER_PART_NUMBER") "835-RT6160AWSC"))
      (libsource (lib "eagle-import") (part "RT6160AWSC_RT6160AWSC"))
    )
    (comp (ref "J2")
      (value "TC2030-IDC")
      (footprint "eagle-import:TC2030-IDC_TC2030IDC")
      (libsource (lib "eagle-import") (part "TC2030-IDC_TC2030-IDC"))
    )
    (comp (ref "L1")
      (value "3.9nH")
      (footprint "eagle-import:NORDIC_NRF_2_RESC0402_L")
      (libsource (lib "eagle-import") (part "NORDIC_NRF_2_INDUCTOR_0402_L"))
    )
    (comp (ref "L2")
      (value "10µH")
      (footprint "eagle-import:NORDIC_NRF_2_RESC0402_L")
      (libsource (lib "eagle-import") (part "NORDIC_NRF_2_INDUCTOR_0402_L"))
    )
    (comp (ref "L3")
      (value "15nH")
      (footprint "eagle-import:NORDIC_NRF_2_RESC0402_L")
      (libsource (lib "eagle-import") (part "NORDIC_NRF_2_INDUCTOR_0402_L"))
    )
    (comp (ref "L7")
      (value "MLP2016SR47MT0S1")
      (footprint "eagle-import:MLP2016SR47MT0S1_INDC2016X100N")
      (fields (field (name "MANUFACTURER_PART_NUMBER") "FTC252012SR47MBCA"))
      (libsource (lib "eagle-import") (part "MLP2016SR47MT0S1_FTC252012SR47MBCA"))
    )
    (comp (ref "R2")
      (value "0")
      (footprint "eagle-import:ERA-1AEB3401C_0201")
      (fields (field (name "RESISTANCE") "0"))
      (libsource (lib "eagle-import") (part "ERA-1AEB3401C_CPF0201D7K68C1"))
    )
    (comp (ref "R3")
      (value "0")
      (footprint "eagle-import:ERA-1AEB3401C_0201")
      (fields (field (name "RESISTANCE") "0"))
      (libsource (lib "eagle-import") (part "ERA-1AEB3401C_CPF0201D7K68C1"))
    )
    (comp (ref "R4")
      (value "0")
      (footprint "eagle-import:ERA-1AEB3401C_0201")
      (fields (field (name "RESISTANCE") "0"))
      (libsource (lib "eagle-import") (part "ERA-1AEB3401C_CPF0201D7K68C1"))
    )
    (comp (ref "R9")
      (value "10k")
      (footprint "eagle-import:ERA-1AEB3401C_0201")
      (fields (field (name "RESISTANCE") "10k"))
      (libsource (lib "eagle-import") (part "ERA-1AEB3401C_CPF0201D7K68C1"))
    )
    (comp (ref "R17")
      (value "3k3")
      (footprint "eagle-import:ERA-1AEB3401C_0201")
      (fields (field (name "RESISTANCE") "3k3"))
      (libsource (lib "eagle-import") (part "ERA-1AEB3401C_CPF0201D7K68C1"))
    )
    (comp (ref "R18")
      (value "3K3")
      (footprint "eagle-import:ERA-1AEB3401C_0201")
      (fields (field (name "RESISTANCE") "3k3"))
      (libsource (lib "eagle-import") (part "ERA-1AEB3401C_CPF0201D7K68C1"))
    )
    (comp (ref "TP_3.3V")
      (value "HECTOR_WATCH_1_TPTP20R")
      (footprint "eagle-import:HECTOR_WATCH_1_TP20R")
      (libsource (lib "eagle-import") (part "HECTOR_WATCH_1_TPTP20R"))
    )
    (comp (ref "TP_3V3")
      (value "HECTOR_WATCH_1_TPTP20R")
      (footprint "eagle-import:HECTOR_WATCH_1_TP20R")
      (libsource (lib "eagle-import") (part "HECTOR_WATCH_1_TPTP20R"))
    )
    (comp (ref "TP_GND")
      (value "HECTOR_WATCH_1_TPTP20R")
      (footprint "eagle-import:HECTOR_WATCH_1_TP20R")
      (libsource (lib "eagle-import") (part "HECTOR_WATCH_1_TPTP20R"))
    )
    (comp (ref "TP_RESET")
      (value "HECTOR_WATCH_1_TPTP20R")
      (footprint "eagle-import:HECTOR_WATCH_1_TP20R")
      (libsource (lib "eagle-import") (part "HECTOR_WATCH_1_TPTP20R"))
    )
    (comp (ref "TP_SCL")
      (value "HECTOR_WATCH_1_TPTP20R")
      (footprint "eagle-import:HECTOR_WATCH_1_TP20R")
      (libsource (lib "eagle-import") (part "HECTOR_WATCH_1_TPTP20R"))
    )
    (comp (ref "TP_SDA")
      (value "HECTOR_WATCH_1_TPTP20R")
      (footprint "eagle-import:HECTOR_WATCH_1_TP20R")
      (libsource (lib "eagle-import") (part "HECTOR_WATCH_1_TPTP20R"))
    )
    (comp (ref "TP_SWDCLK")
      (value "HECTOR_WATCH_1_TPTP20R")
      (footprint "eagle-import:HECTOR_WATCH_1_TP20R")
      (libsource (lib "eagle-import") (part "HECTOR_WATCH_1_TPTP20R"))
    )
    (comp (ref "TP_SWDIO")
      (value "HECTOR_WATCH_1_TPTP20R")
      (footprint "eagle-import:HECTOR_WATCH_1_TP20R")
      (libsource (lib "eagle-import") (part "HECTOR_WATCH_1_TPTP20R"))
    )
    (comp (ref "TP_SWO")
      (value "HECTOR_WATCH_1_TPTP20R")
      (footprint "eagle-import:HECTOR_WATCH_1_TP20R")
      (libsource (lib "eagle-import") (part "HECTOR_WATCH_1_TPTP20R"))
    )
    (comp (ref "TP_VREG")
      (value "HECTOR_WATCH_1_TPTP20R")
      (footprint "eagle-import:HECTOR_WATCH_1_TP20R")
      (libsource (lib "eagle-import") (part "HECTOR_WATCH_1_TPTP20R"))
    )
    (comp (ref "U1")
      (value "NRF52840_QF")
      (footprint "eagle-import:NORDIC_NRF_4_AQFN50P700X700X85_HS-74N")
      (libsource (lib "eagle-import") (part "NORDIC_NRF_4_NRF52840_QF"))
    )
    (comp (ref "X1")
      (value "32MHz")
      (footprint "eagle-import:NORDIC_NRF_BT-XTAL_2016_N")
      (libsource (lib "eagle-import") (part "NORDIC_NRF_XTAL_32MHZ"))
    )
    (comp (ref "X2")
      (value "32.768kHz")
      (footprint "eagle-import:NORDIC_NRF_1_XTAL_3215_N")
      (libsource (lib "eagle-import") (part "NORDIC_NRF_1_XTAL_32KHZ"))
    )
  )
  (nets
    (net (code "1") (name "3V3") (class "Default")
      (node (ref "C12") (pin "1") (pinfunction "1_1") (pintype "passive"))
      (node (ref "C14") (pin "1") (pinfunction "1_1") (pintype "passive"))
      (node (ref "C19") (pin "1") (pinfunction "1_1") (pintype "passive"))
      (node (ref "C25") (pin "1") (pinfunction "1_1") (pintype "passive"))
      (node (ref "C33") (pin "1") (pinfunction "1_1") (pintype "passive"))
      (node (ref "C34") (pin "2") (pinfunction "2_2") (pintype "passive"))
      (node (ref "C6") (pin "1") (pinfunction "1_1") (pintype "passive"))
      (node (ref "C7") (pin "1") (pinfunction "1_1") (pintype "passive"))
      (node (ref "C8") (pin "1") (pinfunction "1_1") (pintype "passive"))
      (node (ref "IC2") (pin "C2") (pinfunction "VDD_C2") (pintype "bidirectional"))
      (node (ref "IC3") (pin "10") (pinfunction "CSB_10") (pintype "bidirectional"))
      (node (ref "IC3") (pin "3") (pinfunction "VDDIO_3") (pintype "bidirectional"))
      (node (ref "IC3") (pin "7") (pinfunction "VDD_7") (pintype "bidirectional"))
      (node (ref "IC9") (pin "E2") (pinfunction "VOUT_1_E2") (pintype "bidirectional"))
      (node (ref "IC9") (pin "E3") (pinfunction "VOUT_2_E3") (pintype "bidirectional"))
      (node (ref "J2") (pin "1") (pinfunction "1_1") (pintype "bidirectional"))
      (node (ref "Q1") (pin "2") (pinfunction "S_2") (pintype "bidirectional"))
      (node (ref "R17") (pin "1") (pinfunction "1_1") (pintype "bidirectional"))
      (node (ref "R18") (pin "1") (pinfunction "1_1") (pintype "bidirectional"))
      (node (ref "R5") (pin "2") (pinfunction "2_2") (pintype "bidirectional"))
      (node (ref "R7") (pin "2") (pinfunction "2_2") (pintype "bidirectional"))
      (node (ref "R8") (pin "1") (pinfunction "1_1") (pintype "bidirectional"))
      (node (ref "R_PWR_EPD") (pin "2") (pinfunction "2_2") (pintype "bidirectional"))
      (node (ref "TP_3.3V") (pin "TP") (pinfunction "TP_TP") (pintype "input"))
      (node (ref "TP_3V3") (pin "TP") (pinfunction "TP_TP") (pintype "input"))
      (node (ref "U1") (pin "P$A22") (pinfunction "VDD_P$A22") (pintype "power_in"))
      (node (ref "U1") (pin "P$AD14") (pinfunction "VDD_P$AD14") (pintype "power_in"))
      (node (ref "U1") (pin "P$AD23") (pinfunction "VDD_P$AD23") (pintype "power_in"))
      (node (ref "U1") (pin "P$B1") (pinfunction "VDD_P$B1") (pintype "power_in"))
      (node (ref "U1") (pin "P$W1") (pinfunction "VDD_P$W1") (pintype "power_in"))
      (node (ref "U1") (pin "P$Y2") (pinfunction "VDDH_P$Y2") (pintype "power_in"))
    )
    (net (code "2") (name "ALERT") (class "Default")
      (node (ref "U1") (pin "P$J24") (pinfunction "P0.10/NFC2_P$J24") (pintype "bidirectional"))
      (node (ref "U3") (pin "5") (pinfunction "~{ALERT}_5") (pintype "output"))
    )
    (net (code "3") (name "D+") (class "Default")
      (node (ref "D3") (pin "4") (pinfunction "I/O2_2_4") (pintype "bidirectional"))
      (node (ref "U1") (pin "P$AD6") (pinfunction "D+_P$AD6") (pintype "bidirectional"))
    )
    (net (code "4") (name "D-") (class "Default")
      (node (ref "D3") (pin "6") (pinfunction "I/O1_2_6") (pintype "bidirectional"))
      (node (ref "U1") (pin "P$AD4") (pinfunction "D-_P$AD4") (pintype "bidirectional"))
    )
    (net (code "5") (name "DEC1") (class "Default")
      (node (ref "C5") (pin "1") (pinfunction "1_1") (pintype "passive"))
      (node (ref "U1") (pin "P$C1") (pinfunction "DEC1_P$C1") (pintype "power_in"))
    )
    (net (code "6") (name "DN") (class "Default")
      (node (ref "D3") (pin "1") (pinfunction "I/O1_1_1") (pintype "bidirectional"))
      (node (ref "J4") (pin "A7") (pinfunction "DN1_A7") (pintype "bidirectional"))
      (node (ref "J4") (pin "B7") (pinfunction "DN2_B7") (pintype "bidirectional"))
    )
    (net (code "7") (name "DP") (class "Default")
      (node (ref "D3") (pin "3") (pinfunction "I/O2_1_3") (pintype "bidirectional"))
      (node (ref "J4") (pin "A6") (pinfunction "DP1_A6") (pintype "bidirectional"))
      (node (ref "J4") (pin "B6") (pinfunction "DP2_B6") (pintype "bidirectional"))
    )
    (net (code "8") (name "EPD_3V3") (class "Default")
      (node (ref "C1-EP-DR") (pin "1") (pinfunction "1_1") (pintype "passive"))
      (node (ref "EPD_C5") (pin "2") (pinfunction "2_2") (pintype "passive"))
      (node (ref "J1") (pin "15") (pinfunction "15_15") (pintype "bidirectional"))
      (node (ref "J1") (pin "16") (pinfunction "16_16") (pintype "bidirectional"))
      (node (ref "L5") (pin "2") (pinfunction "2_2") (pintype "passive"))
      (node (ref "Q1") (pin "3") (pinfunction "D_3") (pintype "bidirectional"))
    )
    (net (code "9") (name "EPD_BUSY") (class "Default")
      (node (ref "J1") (pin "9") (pinfunction "9_9") (pintype "bidirectional"))
      (node (ref "U1") (pin "P$AD12") (pinfunction "P0.17_P$AD12") (pintype "bidirectional"))
    )
    (net (code "10") (name "EPD_CS") (class "Default")
      (node (ref "J1") (pin "12") (pinfunction "12_12") (pintype "bidirectional"))
      (node (ref "U1") (pin "P$K2") (pinfunction "P0.05/AIN3_P$K2") (pintype "bidirectional"))
    )
    (net (code "11") (name "EPD_DC") (class "Default")
      (node (ref "J1") (pin "11") (pinfunction "11_11") (pintype "bidirectional"))
      (node (ref "U1") (pin "P$AD10") (pinfunction "P0.15_P$AD10") (pintype "bidirectional"))
    )
    (net (code "12") (name "EPD_RST") (class "Default")
      (node (ref "J1") (pin "10") (pinfunction "10_10") (pintype "bidirectional"))
      (node (ref "U1") (pin "P$AC11") (pinfunction "P0.16_P$AC11") (pintype "bidirectional"))
    )
    (net (code "13") (name "GDR") (class "Default")
      (node (ref "J1") (pin "2") (pinfunction "2_2") (pintype "bidirectional"))
      (node (ref "Q3") (pin "1") (pinfunction "G_1") (pintype "bidirectional"))
      (node (ref "R2_EP_DR") (pin "2") (pinfunction "2_2") (pintype "bidirectional"))
    )
    (net (code "14") (name "GND") (class "Default")
      (node (ref "C1-EP-DR") (pin "2") (pinfunction "2_2") (pintype "passive"))
      (node (ref "C10") (pin "2") (pinfunction "2_2") (pintype "passive"))
      (node (ref "C11") (pin "2") (pinfunction "2_2") (pintype "passive"))
      (node (ref "C12") (pin "2") (pinfunction "2_2") (pintype "passive"))
      (node (ref "C13") (pin "2") (pinfunction "2_2") (pintype "passive"))
      (node (ref "C14") (pin "2") (pinfunction "2_2") (pintype "passive"))
      (node (ref "C17") (pin "1") (pinfunction "1_1") (pintype "passive"))
      (node (ref "C18") (pin "1") (pinfunction "1_1") (pintype "passive"))
      (node (ref "C19") (pin "2") (pinfunction "2_2") (pintype "passive"))
      (node (ref "C20") (pin "2") (pinfunction "2_2") (pintype "passive"))
      (node (ref "C21") (pin "2") (pinfunction "2_2") (pintype "passive"))
      (node (ref "C22") (pin "2") (pinfunction "2_2") (pintype "passive"))
      (node (ref "C23") (pin "1") (pinfunction "1_1") (pintype "passive"))
      (node (ref "C24") (pin "1") (pinfunction "1_1") (pintype "passive"))
      (node (ref "C25") (pin "2") (pinfunction "2_2") (pintype "passive"))
      (node (ref "C27") (pin "1") (pinfunction "1_1") (pintype "passive"))
      (node (ref "C29") (pin "1") (pinfunction "1_1") (pintype "passive"))
      (node (ref "C3") (pin "2") (pinfunction "2_2") (pintype "passive"))
      (node (ref "C30") (pin "1") (pinfunction "1_1") (pintype "passive"))
      (node (ref "C31") (pin "1") (pinfunction "1_1") (pintype "passive"))
      (node (ref "C32") (pin "1") (pinfunction "1_1") (pintype "passive"))
      (node (ref "C33") (pin "2") (pinfunction "2_2") (pintype "passive"))
      (node (ref "C34") (pin "1") (pinfunction "1_1") (pintype "passive"))
      (node (ref "C37") (pin "1") (pinfunction "1_1") (pintype "passive"))
      (node (ref "C38") (pin "1") (pinfunction "1_1") (pintype "passive"))
      (node (ref "C39") (pin "2") (pinfunction "2_2") (pintype "passive"))
      (node (ref "C4") (pin "2") (pinfunction "2_2") (pintype "passive"))
      (node (ref "C42") (pin "2") (pinfunction "2_2") (pintype "passive"))
      (node (ref "C43") (pin "2") (pinfunction "2_2") (pintype "passive"))
      (node (ref "C5") (pin "2") (pinfunction "2_2") (pintype "passive"))
      (node (ref "C6") (pin "2") (pinfunction "2_2") (pintype "passive"))
      (node (ref "C7") (pin "2") (pinfunction "2_2") (pintype "passive"))
      (node (ref "C8") (pin "2") (pinfunction "2_2") (pintype "passive"))
      (node (ref "C9") (pin "2") (pinfunction "2_2") (pintype "passive"))
      (node (ref "D3") (pin "2") (pinfunction "GND_2") (pintype "bidirectional"))
      (node (ref "D4") (pin "1") (pinfunction "K_1") (pintype "bidirectional"))
      (node (ref "EPD_C1") (pin "1") (pinfunction "1_1") (pintype "passive"))
      (node (ref "EPD_C10") (pin "1") (pinfunction "1_1") (pintype "passive"))
      (node (ref "EPD_C11") (pin "1") (pinfunction "1_1") (pintype "passive"))
      (node (ref "EPD_C12") (pin "1") (pinfunction "1_1") (pintype "passive"))
      (node (ref "EPD_C2") (pin "1") (pinfunction "1_1") (pintype "passive"))
      (node (ref "EPD_C5") (pin "1") (pinfunction "1_1") (pintype "passive"))
      (node (ref "EPD_C6") (pin "1") (pinfunction "1_1") (pintype "passive"))
      (node (ref "EPD_C7") (pin "1") (pinfunction "1_1") (pintype "passive"))
      (node (ref "EPD_C8") (pin "1") (pinfunction "1_1") (pintype "passive"))
      (node (ref "EPD_C9") (pin "1") (pinfunction "1_1") (pintype "passive"))
      (node (ref "IC1") (pin "D2") (pinfunction "GND_D2") (pintype "bidirectional"))
      (node (ref "IC2") (pin "B1") (pinfunction "IN/TRIG_B1") (pintype "bidirectional"))
      (node (ref "IC2") (pin "B3") (pinfunction "GND_B3") (pintype "bidirectional"))
      (node (ref "IC3") (pin "8") (pinfunction "GNDIO_8") (pintype "bidirectional"))
      (node (ref "IC3") (pin "9") (pinfunction "GND_9") (pintype "bidirectional"))
      (node (ref "IC9") (pin "B1") (pinfunction "VSEL_B1") (pintype "bidirectional"))
      (node (ref "IC9") (pin "C2") (pinfunction "PGND_1_C2") (pintype "bidirectional"))
      (node (ref "IC9") (pin "C3") (pinfunction "PGND_2_C3") (pintype "bidirectional"))
      (node (ref "J1") (pin "17") (pinfunction "17_17") (pintype "bidirectional"))
      (node (ref "J1") (pin "8") (pinfunction "8_8") (pintype "bidirectional"))
      (node (ref "J1") (pin "MP1") (pinfunction "MP1_MP1") (pintype "bidirectional"))
      (node (ref "J1") (pin "MP2") (pinfunction "MP2_MP2") (pintype "bidirectional"))
      (node (ref "J2") (pin "3") (pinfunction "3_3") (pintype "bidirectional"))
      (node (ref "J2") (pin "5") (pinfunction "5_5") (pintype "bidirectional"))
      (node (ref "J4") (pin "A12_B1") (pinfunction "GND_A12_B1") (pintype "power_in"))
      (node (ref "J4") (pin "A1_B12") (pinfunction "GND_A1_B12") (pintype "power_in"))
      (node (ref "J4") (pin "SH1") (pinfunction "SHIELD_SH1") (pintype "passive"))
      (node (ref "J4") (pin "SH2") (pinfunction "SHIELD_SH2") (pintype "passive"))
      (node (ref "J4") (pin "SH3") (pinfunction "SHIELD_SH3") (pintype "passive"))
      (node (ref "J4") (pin "SH4") (pinfunction "SHIELD_SH4") (pintype "passive"))
      (node (ref "R1_USB") (pin "1") (pinfunction "1_1") (pintype "bidirectional"))
      (node (ref "R2_EP_DR") (pin "1") (pinfunction "1_1") (pintype "bidirectional"))
      (node (ref "R2_USB") (pin "2") (pinfunction "2_2") (pintype "bidirectional"))
      (node (ref "R3") (pin "2") (pinfunction "2_2") (pintype "bidirectional"))
      (node (ref "R9") (pin "1") (pinfunction "1_1") (pintype "bidirectional"))
      (node (ref "R_TYPE_SEL") (pin "1") (pinfunction "1_1") (pintype "bidirectional"))
      (node (ref "SJ1") (pin "1") (pinfunction "1_1") (pintype "passive"))
      (node (ref "SW_DN") (pin "1") (pinfunction "1_1") (pintype "passive"))
      (node (ref "SW_ENT") (pin "1") (pinfunction "1_1") (pintype "passive"))
      (node (ref "SW_UP") (pin "1") (pinfunction "1_1") (pintype "passive"))
      (node (ref "TP_BAT_GND") (pin "TP") (pinfunction "TP_TP") (pintype "input"))
      (node (ref "TP_GND") (pin "TP") (pinfunction "TP_TP") (pintype "input"))
      (node (ref "U1") (pin "P$74") (pinfunction "VSS_PAD_P$74") (pintype "bidirectional"))
      (node (ref "U1") (pin "P$75") (pinfunction "VSS_PAD_P$75") (pintype "bidirectional"))
      (node (ref "U1") (pin "P$76") (pinfunction "VSS_PAD_P$76") (pintype "bidirectional"))
      (node (ref "U1") (pin "P$77") (pinfunction "VSS_PAD_P$77") (pintype "bidirectional"))
      (node (ref "U1") (pin "P$78") (pinfunction "VSS_PAD_P$78") (pintype "bidirectional"))
      (node (ref "U1") (pin "P$79") (pinfunction "VSS_PAD_P$79") (pintype "bidirectional"))
      (node (ref "U1") (pin "P$80") (pinfunction "VSS_PAD_P$80") (pintype "bidirectional"))
      (node (ref "U1") (pin "P$81") (pinfunction "VSS_PAD_P$81") (pintype "bidirectional"))
      (node (ref "U1") (pin "P$82") (pinfunction "VSS_PAD_P$82") (pintype "bidirectional"))
      (node (ref "U1") (pin "P$83") (pinfunction "VSS_PAD_P$83") (pintype "bidirectional"))
      (node (ref "U1") (pin "P$84") (pinfunction "VSS_PAD_P$84") (pintype "bidirectional"))
      (node (ref "U1") (pin "P$85") (pinfunction "VSS_PAD_P$85") (pintype "bidirectional"))
      (node (ref "U1") (pin "P$86") (pinfunction "VSS_PAD_P$86") (pintype "bidirectional"))
      (node (ref "U1") (pin "P$87") (pinfunction "VSS_PAD_P$87") (pintype "bidirectional"))
      (node (ref "U1") (pin "P$88") (pinfunction "VSS_PAD_P$88") (pintype "bidirectional"))
      (node (ref "U1") (pin "P$89") (pinfunction "VSS_PAD_P$89") (pintype "bidirectional"))
      (node (ref "U1") (pin "P$90") (pinfunction "VSS_PAD_P$90") (pintype "bidirectional"))
      (node (ref "U1") (pin "P$F23") (pinfunction "VSS_PA_P$F23") (pintype "bidirectional"))
      (node (ref "U3") (pin "1") (pinfunction "CTG_1") (pintype "power_in"))
      (node (ref "U3") (pin "4") (pinfunction "GND_4") (pintype "power_in"))
      (node (ref "U3") (pin "6") (pinfunction "QSTRT_6") (pintype "input"))
      (node (ref "U3") (pin "9") (pinfunction "EP_9") (pintype "power_in"))
    )
    (net (code "15") (name "HAPTIC_EN") (class "Default")
      (node (ref "IC2") (pin "A1") (pinfunction "EN_A1") (pintype "bidirectional"))
      (node (ref "U1") (pin "P$U1") (pinfunction "P0.12_P$U1") (pintype "bidirectional"))
    )
    (net (code "16") (name "IMU_INT1") (class "Default")
      (node (ref "IC3") (pin "5") (pinfunction "INT1_5") (pintype "bidirectional"))
      (node (ref "U1") (pin "P$N1") (pinfunction "P0.08_P$N1") (pintype "bidirectional"))
    )
    (net (code "17") (name "IMU_INT2") (class "Default")
      (node (ref "IC3") (pin "6") (pinfunction "INT2_6") (pintype "bidirectional"))
      (node (ref "U1") (pin "P$P2") (pinfunction "P1.08_P$P2") (pintype "bidirectional"))
    )
    (net (code "18") (name "LX1") (class "Default")
      (node (ref "IC9") (pin "B2") (pinfunction "SW1_1_B2") (pintype "bidirectional"))
      (node (ref "IC9") (pin "B3") (pinfunction "SW1_2_B3") (pintype "bidirectional"))
      (node (ref "L7") (pin "1") (pinfunction "1_1") (pintype "bidirectional"))
    )
    (net (code "19") (name "LX2") (class "Default")
      (node (ref "IC9") (pin "D2") (pinfunction "SW2_1_D2") (pintype "bidirectional"))
      (node (ref "IC9") (pin "D3") (pinfunction "SW2_2_D3") (pintype "bidirectional"))
      (node (ref "L7") (pin "2") (pinfunction "2_2") (pintype "bidirectional"))
    )
    (net (code "20") (name "MOSI") (class "Default")
      (node (ref "J1") (pin "14") (pinfunction "14_14") (pintype "bidirectional"))
      (node (ref "U1") (pin "P$B13") (pinfunction "P0.03/AIN1_P$B13") (pintype "bidirectional"))
    )
    (net (code "21") (name "Net-(ANT1-FEED)") (class "Default")
      (node (ref "ANT1") (pin "1") (pinfunction "FEED_1") (pintype "input"))
      (node (ref "C22") (pin "1") (pinfunction "1_1") (pintype "passive"))
      (node (ref "C4") (pin "1") (pinfunction "1_1") (pintype "passive"))
      (node (ref "L1") (pin "2") (pinfunction "2_2") (pintype "passive"))
    )
    (net (code "22") (name "Net-(C1-Pad2)") (class "Default")
      (node (ref "C1") (pin "2") (pinfunction "2_2") (pintype "passive"))
      (node (ref "X1") (pin "2") (pinfunction "2_2") (pintype "passive"))
    )
    (net (code "23") (name "Net-(C2-Pad2)") (class "Default")
      (node (ref "C2") (pin "2") (pinfunction "2_2") (pintype "passive"))
      (node (ref "X1") (pin "4") (pinfunction "4_4") (pintype "passive"))
    )
    (net (code "24") (name "Net-(D2-K)") (class "Default")
      (node (ref "C2-EP-DR") (pin "1") (pinfunction "1_1") (pintype "passive"))
      (node (ref "D2") (pin "1") (pinfunction "K_1") (pintype "bidirectional"))
      (node (ref "D4") (pin "2") (pinfunction "A_2") (pintype "bidirectional"))
    )
    (net (code "25") (name "Net-(D5-A)") (class "Default")
      (node (ref "C2-EP-DR") (pin "2") (pinfunction "2_2") (pintype "passive"))
      (node (ref "D5") (pin "2") (pinfunction "A_2") (pintype "bidirectional"))
      (node (ref "L5") (pin "1") (pinfunction "1_1") (pintype "passive"))
      (node (ref "Q3") (pin "3") (pinfunction "D_3") (pintype "bidirectional"))
    )
    (net (code "26") (name "Net-(EPD_C1-Pad2)") (class "Default")
      (node (ref "EPD_C1") (pin "2") (pinfunction "2_2") (pintype "passive"))
      (node (ref "J1") (pin "5") (pinfunction "5_5") (pintype "bidirectional"))
    )
    (net (code "27") (name "Net-(EPD_C2-Pad2)") (class "Default")
      (node (ref "EPD_C2") (pin "2") (pinfunction "2_2") (pintype "passive"))
      (node (ref "J1") (pin "4") (pinfunction "4_4") (pintype "bidirectional"))
    )
    (net (code "28") (name "Net-(EPD_C6-Pad2)") (class "Default")
      (node (ref "EPD_C6") (pin "2") (pinfunction "2_2") (pintype "passive"))
      (node (ref "J1") (pin "18") (pinfunction "18_18") (pintype "bidirectional"))
    )
    (net (code "29") (name "Net-(EPD_C7-Pad2)") (class "Default")
      (node (ref "EPD_C7") (pin "2") (pinfunction "2_2") (pintype "passive"))
      (node (ref "J1") (pin "19") (pinfunction "19_19") (pintype "bidirectional"))
    )
    (net (code "30") (name "Net-(EPD_C8-Pad2)") (class "Default")
      (node (ref "EPD_C8") (pin "2") (pinfunction "2_2") (pintype "passive"))
      (node (ref "J1") (pin "20") (pinfunction "20_20") (pintype "bidirectional"))
    )
    (net (code "31") (name "Net-(EPD_C10-Pad2)") (class "Default")
      (node (ref "EPD_C10") (pin "2") (pinfunction "2_2") (pintype "passive"))
      (node (ref "J1") (pin "22") (pinfunction "22_22") (pintype "bidirectional"))
    )
    (net (code "32") (name "Net-(EPD_C12-Pad2)") (class "Default")
      (node (ref "EPD_C12") (pin "2") (pinfunction "2_2") (pintype "passive"))
      (node (ref "J1") (pin "24") (pinfunction "24_24") (pintype "bidirectional"))
    )
    (net (code "33") (name "Net-(IC1-TS{slash}MR)") (class "Default")
      (node (ref "IC1") (pin "D1") (pinfunction "TS/MR_D1") (pintype "bidirectional"))
      (node (ref "R9") (pin "2") (pinfunction "2_2") (pintype "bidirectional"))
    )
    (net (code "34") (name "Net-(IC2-REG)") (class "Default")
      (node (ref "C32") (pin "2") (pinfunction "2_2") (pintype "passive"))
      (node (ref "IC2") (pin "A2") (pinfunction "REG_A2") (pintype "bidirectional"))
    )
    (net (code "35") (name "Net-(IC3-SDO)") (class "Default")
      (node (ref "IC3") (pin "1") (pinfunction "SDO_1") (pintype "bidirectional"))
      (node (ref "R3") (pin "1") (pinfunction "1_1") (pintype "bidirectional"))
    )
    (net (code "36") (name "Net-(IC9-SCL)") (class "Default")
      (node (ref "IC9") (pin "D1") (pinfunction "SCL_D1") (pintype "bidirectional"))
      (node (ref "R4") (pin "2") (pinfunction "2_2") (pintype "bidirectional"))
    )
    (net (code "37") (name "Net-(IC9-SDA)") (class "Default")
      (node (ref "IC9") (pin "E1") (pinfunction "SDA_E1") (pintype "bidirectional"))
      (node (ref "R2") (pin "2") (pinfunction "2_2") (pintype "bidirectional"))
    )
    (net (code "38") (name "Net-(J4-CC1)") (class "Default")
      (node (ref "J4") (pin "A5") (pinfunction "CC1_A5") (pintype "bidirectional"))
      (node (ref "R1_USB") (pin "2") (pinfunction "2_2") (pintype "bidirectional"))
    )
    (net (code "39") (name "Net-(J4-CC2)") (class "Default")
      (node (ref "J4") (pin "B5") (pinfunction "CC2_B5") (pintype "bidirectional"))
      (node (ref "R2_USB") (pin "1") (pinfunction "1_1") (pintype "bidirectional"))
    )
    (net (code "40") (name "Net-(L2-Pad2)") (class "Default")
      (node (ref "L2") (pin "2") (pinfunction "2_2") (pintype "passive"))
      (node (ref "L3") (pin "1") (pinfunction "1_1") (pintype "passive"))
    )
    (net (code "41") (name "Net-(R1_EP_DR-Pad1)") (class "Default")
      (node (ref "R1_EP_DR") (pin "1") (pinfunction "1_1") (pintype "bidirectional"))
      (node (ref "R_TYPE_SEL") (pin "2") (pinfunction "2_2") (pintype "bidirectional"))
      (node (ref "SJ1") (pin "2") (pinfunction "2_2") (pintype "passive"))
    )
    (net (code "42") (name "Net-(U1-ANT)") (class "Default")
      (node (ref "C3") (pin "1") (pinfunction "1_1") (pintype "passive"))
      (node (ref "L1") (pin "1") (pinfunction "1_1") (pintype "passive"))
      (node (ref "U1") (pin "P$H23") (pinfunction "ANT_P$H23") (pintype "bidirectional"))
    )
    (net (code "43") (name "Net-(U1-DCC)") (class "Default")
      (node (ref "L2") (pin "1") (pinfunction "1_1") (pintype "passive"))
      (node (ref "U1") (pin "P$B3") (pinfunction "DCC_P$B3") (pintype "output"))
    )
    (net (code "44") (name "Net-(U1-DEC2)") (class "Default")
      (node (ref "C13") (pin "1") (pinfunction "1_1") (pintype "passive"))
      (node (ref "U1") (pin "P$A18") (pinfunction "DEC2_P$A18") (pintype "bidirectional"))
    )
    (net (code "45") (name "Net-(U1-DEC3)") (class "Default")
      (node (ref "C11") (pin "1") (pinfunction "1_1") (pintype "passive"))
      (node (ref "U1") (pin "P$D23") (pinfunction "DEC3_P$D23") (pintype "bidirectional"))
    )
    (net (code "46") (name "Net-(U1-DEC3V3)") (class "Default")
      (node (ref "C20") (pin "1") (pinfunction "1_1") (pintype "passive"))
      (node (ref "U1") (pin "P$AC5") (pinfunction "DEC3V3_P$AC5") (pintype "bidirectional"))
    )
    (net (code "47") (name "Net-(U1-DEC4)") (class "Default")
      (node (ref "C10") (pin "1") (pinfunction "1_1") (pintype "passive"))
      (node (ref "C15") (pin "1") (pinfunction "1_1") (pintype "passive"))
      (node (ref "C16") (pin "1") (pinfunction "1_1") (pintype "passive"))
      (node (ref "L3") (pin "2") (pinfunction "2_2") (pintype "passive"))
      (node (ref "U1") (pin "P$B5") (pinfunction "DEC4_P$B5") (pintype "power_in"))
      (node (ref "U1") (pin "P$E24") (pinfunction "DEC6_P$E24") (pintype "bidirectional"))
    )
    (net (code "48") (name "Net-(U1-DEC5)") (class "Default")
      (node (ref "C9") (pin "1") (pinfunction "1_1") (pintype "passive"))
      (node (ref "U1") (pin "P$N24") (pinfunction "DEC5_P$N24") (pintype "bidirectional"))
    )
    (net (code "49") (name "Net-(U1-VSS)") (class "Default")
      (node (ref "C15") (pin "2") (pinfunction "2_2") (pintype "passive"))
      (node (ref "C16") (pin "2") (pinfunction "2_2") (pintype "passive"))
      (node (ref "U1") (pin "P$B7") (pinfunction "VSS_P$B7") (pintype "power_in"))
    )
    (net (code "50") (name "Net-(U1-XC1)") (class "Default")
      (node (ref "C1") (pin "1") (pinfunction "1_1") (pintype "passive"))
      (node (ref "U1") (pin "P$B24") (pinfunction "XC1_P$B24") (pintype "input"))
      (node (ref "X1") (pin "1") (pinfunction "1_1") (pintype "passive"))
    )
    (net (code "51") (name "Net-(U1-XC2)") (class "Default")
      (node (ref "C2") (pin "1") (pinfunction "1_1") (pintype "passive"))
      (node (ref "U1") (pin "P$A23") (pinfunction "XC2_P$A23") (pintype "output"))
      (node (ref "X1") (pin "3") (pinfunction "3_3") (pintype "passive"))
    )
    (net (code "52") (name "OUT+") (class "Default")
      (node (ref "IC2") (pin "A3") (pinfunction "OUT+_A3") (pintype "bidirectional"))
      (node (ref "TP_OP") (pin "TP") (pinfunction "TP_TP") (pintype "input"))
    )
    (net (code "53") (name "OUT-") (class "Default")
      (node (ref "IC2") (pin "C3") (pinfunction "OUT-_C3") (pintype "bidirectional"))
      (node (ref "TP_ON") (pin "TP") (pinfunction "TP_TP") (pintype "input"))
    )
    (net (code "54") (name "P0.00{slash}XL1") (class "Default")
      (node (ref "C17") (pin "2") (pinfunction "2_2") (pintype "passive"))
      (node (ref "U1") (pin "P$D2") (pinfunction "P0.00/XL1_P$D2") (pintype "bidirectional"))
      (node (ref "X2") (pin "2") (pinfunction "2_2") (pintype "passive"))
    )
    (net (code "55") (name "P0.00{slash}XL2") (class "Default")
      (node (ref "C18") (pin "2") (pinfunction "2_2") (pintype "passive"))
      (node (ref "U1") (pin "P$F2") (pinfunction "P0.01/XL2_P$F2") (pintype "bidirectional"))
      (node (ref "X2") (pin "1") (pinfunction "1_1") (pintype "passive"))
    )
    (net (code "56") (name "P0.04") (class "Default")
      (node (ref "U1") (pin "P$J1") (pinfunction "P0.04/AIN2_P$J1") (pintype "bidirectional"))
    )
    (net (code "57") (name "P0.09") (class "Default")
      (node (ref "U1") (pin "P$L24") (pinfunction "P0.09/NFC1_P$L24") (pintype "bidirectional"))
    )
    (net (code "58") (name "P0.13") (class "Default")
      (node (ref "C30") (pin "2") (pinfunction "2_2") (pintype "passive"))
      (node (ref "R5") (pin "1") (pinfunction "1_1") (pintype "bidirectional"))
      (node (ref "SW_UP") (pin "2") (pinfunction "2_2") (pintype "passive"))
      (node (ref "U1") (pin "P$AD8") (pinfunction "P0.13_P$AD8") (pintype "bidirectional"))
    )
    (net (code "59") (name "P0.14") (class "Default")
      (node (ref "C31") (pin "2") (pinfunction "2_2") (pintype "passive"))
      (node (ref "R8") (pin "2") (pinfunction "2_2") (pintype "bidirectional"))
      (node (ref "SW_ENT") (pin "2") (pinfunction "2_2") (pintype "passive"))
      (node (ref "U1") (pin "P$AC9") (pinfunction "P0.14_P$AC9") (pintype "bidirectional"))
    )
    (net (code "60") (name "P0.19") (class "Default")
      (node (ref "U1") (pin "P$AC15") (pinfunction "P0.19_P$AC15") (pintype "bidirectional"))
    )
    (net (code "61") (name "P0.20") (class "Default")
      (node (ref "U1") (pin "P$AD16") (pinfunction "P0.20_P$AD16") (pintype "bidirectional"))
    )
    (net (code "62") (name "P0.21") (class "Default")
      (node (ref "U1") (pin "P$AC17") (pinfunction "P0.21_P$AC17") (pintype "bidirectional"))
    )
    (net (code "63") (name "P0.22") (class "Default")
      (node (ref "U1") (pin "P$AD18") (pinfunction "P0.22_P$AD18") (pintype "bidirectional"))
    )
    (net (code "64") (name "P0.23") (class "Default")
      (node (ref "U1") (pin "P$AC19") (pinfunction "P0.23_P$AC19") (pintype "bidirectional"))
    )
    (net (code "65") (name "P0.24") (class "Default")
      (node (ref "U1") (pin "P$AD20") (pinfunction "P0.24_P$AD20") (pintype "bidirectional"))
    )
    (net (code "66") (name "P0.25") (class "Default")
      (node (ref "U1") (pin "P$AC21") (pinfunction "P0.25_P$AC21") (pintype "bidirectional"))
    )
    (net (code "67") (name "P0.26") (class "Default")
      (node (ref "U1") (pin "P$G1") (pinfunction "P0.26_P$G1") (pintype "bidirectional"))
    )
    (net (code "68") (name "P0.27") (class "Default")
      (node (ref "U1") (pin "P$H2") (pinfunction "P0.27_P$H2") (pintype "bidirectional"))
    )
    (net (code "69") (name "P0.28") (class "Default")
      (node (ref "U1") (pin "P$B11") (pinfunction "P0.28/AIN4_P$B11") (pintype "bidirectional"))
    )
    (net (code "70") (name "P0.29") (class "Default")
      (node (ref "U1") (pin "P$A10") (pinfunction "P0.29/AIN5_P$A10") (pintype "bidirectional"))
    )
    (net (code "71") (name "P0.30") (class "Default")
      (node (ref "U1") (pin "P$B9") (pinfunction "P0.30/AIN6_P$B9") (pintype "bidirectional"))
    )
    (net (code "72") (name "P0.31") (class "Default")
      (node (ref "U1") (pin "P$A8") (pinfunction "P0.31/AIN7_P$A8") (pintype "bidirectional"))
    )
    (net (code "73") (name "P1.01") (class "Default")
      (node (ref "Q1") (pin "1") (pinfunction "G_1") (pintype "bidirectional"))
      (node (ref "R_PWR_EPD") (pin "1") (pinfunction "1_1") (pintype "bidirectional"))
      (node (ref "U1") (pin "P$Y23") (pinfunction "P1.01_P$Y23") (pintype "bidirectional"))
    )
    (net (code "74") (name "P1.02") (class "Default")
      (node (ref "C29") (pin "2") (pinfunction "2_2") (pintype "passive"))
      (node (ref "R7") (pin "1") (pinfunction "1_1") (pintype "bidirectional"))
      (node (ref "SW_DN") (pin "2") (pinfunction "2_2") (pintype "passive"))
      (node (ref "U1") (pin "P$W24") (pinfunction "P1.02_P$W24") (pintype "bidirectional"))
    )
    (net (code "75") (name "P1.03") (class "Default")
      (node (ref "U1") (pin "P$V23") (pinfunction "P1.03_P$V23") (pintype "bidirectional"))
    )
    (net (code "76") (name "P1.04") (class "Default")
      (node (ref "U1") (pin "P$U24") (pinfunction "P1.04_P$U24") (pintype "bidirectional"))
    )
    (net (code "77") (name "P1.05") (class "Default")
      (node (ref "U1") (pin "P$T23") (pinfunction "P1.05_P$T23") (pintype "bidirectional"))
    )
    (net (code "78") (name "P1.06") (class "Default")
      (node (ref "U1") (pin "P$R24") (pinfunction "P1.06_P$R24") (pintype "bidirectional"))
    )
    (net (code "79") (name "P1.07") (class "Default")
      (node (ref "U1") (pin "P$P23") (pinfunction "P1.07_P$P23") (pintype "bidirectional"))
    )
    (net (code "80") (name "P1.09") (class "Default")
      (node (ref "U1") (pin "P$R1") (pinfunction "P1.09_P$R1") (pintype "bidirectional"))
    )
    (net (code "81") (name "P1.10") (class "Default")
      (node (ref "U1") (pin "P$A20") (pinfunction "P1.10_P$A20") (pintype "bidirectional"))
    )
    (net (code "82") (name "P1.11") (class "Default")
      (node (ref "U1") (pin "P$B19") (pinfunction "P1.11_P$B19") (pintype "bidirectional"))
    )
    (net (code "83") (name "P1.12") (class "Default")
      (node (ref "U1") (pin "P$B17") (pinfunction "P1.12_P$B17") (pintype "bidirectional"))
    )
    (net (code "84") (name "P1.13") (class "Default")
      (node (ref "U1") (pin "P$A16") (pinfunction "P1.13_P$A16") (pintype "bidirectional"))
    )
    (net (code "85") (name "P1.14") (class "Default")
      (node (ref "U1") (pin "P$B15") (pinfunction "P1.14_P$B15") (pintype "bidirectional"))
    )
    (net (code "86") (name "P1.15") (class "Default")
      (node (ref "U1") (pin "P$A14") (pinfunction "P1.15_P$A14") (pintype "bidirectional"))
    )
    (net (code "87") (name "PMIC_INT") (class "Default")
      (node (ref "IC1") (pin "A1") (pinfunction "~{INT}_A1") (pintype "bidirectional"))
      (node (ref "U1") (pin "P$T2") (pinfunction "P0.11_P$T2") (pintype "bidirectional"))
    )
    (net (code "88") (name "PREVGH") (class "Default")
      (node (ref "D5") (pin "1") (pinfunction "K_1") (pintype "bidirectional"))
      (node (ref "EPD_C9") (pin "2") (pinfunction "2_2") (pintype "passive"))
      (node (ref "J1") (pin "21") (pinfunction "21_21") (pintype "bidirectional"))
    )
    (net (code "89") (name "PREVGL") (class "Default")
      (node (ref "D2") (pin "2") (pinfunction "A_2") (pintype "bidirectional"))
      (node (ref "EPD_C11") (pin "2") (pinfunction "2_2") (pintype "passive"))
      (node (ref "J1") (pin "23") (pinfunction "23_23") (pintype "bidirectional"))
    )
    (net (code "90") (name "RESE") (class "Default")
      (node (ref "J1") (pin "3") (pinfunction "3_3") (pintype "bidirectional"))
      (node (ref "Q3") (pin "2") (pinfunction "S_2") (pintype "bidirectional"))
      (node (ref "R1_EP_DR") (pin "2") (pinfunction "2_2") (pintype "bidirectional"))
    )
    (net (code "91") (name "RESET") (class "Default")
      (node (ref "J2") (pin "6") (pinfunction "6_6") (pintype "bidirectional"))
      (node (ref "TP_RESET") (pin "TP") (pinfunction "TP_TP") (pintype "input"))
      (node (ref "U1") (pin "P$AC13") (pinfunction "P0.18/RESET_P$AC13") (pintype "bidirectional"))
    )
    (net (code "92") (name "SCK") (class "Default")
      (node (ref "J1") (pin "13") (pinfunction "13_13") (pintype "bidirectional"))
      (node (ref "U1") (pin "P$A12") (pinfunction "P0.02/AIN0_P$A12") (pintype "bidirectional"))
    )
    (net (code "93") (name "SCL") (class "Default")
      (node (ref "IC1") (pin "B1") (pinfunction "SCL_B1") (pintype "bidirectional"))
      (node (ref "IC2") (pin "C1") (pinfunction "SCL_C1") (pintype "bidirectional"))
      (node (ref "IC3") (pin "12") (pinfunction "SCX_12") (pintype "bidirectional"))
      (node (ref "R17") (pin "2") (pinfunction "2_2") (pintype "bidirectional"))
      (node (ref "R4") (pin "1") (pinfunction "1_1") (pintype "bidirectional"))
      (node (ref "TP_SCL") (pin "TP") (pinfunction "TP_TP") (pintype "input"))
      (node (ref "U1") (pin "P$M2") (pinfunction "P0.07_P$M2") (pintype "bidirectional"))
      (node (ref "U3") (pin "7") (pinfunction "SCL_7") (pintype "input"))
    )
    (net (code "94") (name "SDA") (class "Default")
      (node (ref "IC1") (pin "C1") (pinfunction "SDA_C1") (pintype "bidirectional"))
      (node (ref "IC2") (pin "B2") (pinfunction "SDA_B2") (pintype "bidirectional"))
      (node (ref "IC3") (pin "2") (pinfunction "SDX_2") (pintype "bidirectional"))
      (node (ref "R18") (pin "2") (pinfunction "2_2") (pintype "bidirectional"))
      (node (ref "R2") (pin "1") (pinfunction "1_1") (pintype "bidirectional"))
      (node (ref "TP_SDA") (pin "TP") (pinfunction "TP_TP") (pintype "input"))
      (node (ref "U1") (pin "P$L1") (pinfunction "P0.06_P$L1") (pintype "bidirectional"))
      (node (ref "U3") (pin "8") (pinfunction "SDA_8") (pintype "bidirectional"))
    )
    (net (code "95") (name "SWDCLK") (class "Default")
      (node (ref "J2") (pin "4") (pinfunction "4_4") (pintype "bidirectional"))
      (node (ref "TP_SWDCLK") (pin "TP") (pinfunction "TP_TP") (pintype "input"))
      (node (ref "U1") (pin "P$AA24") (pinfunction "SWDCLK_P$AA24") (pintype "input"))
    )
    (net (code "96") (name "SWDIO") (class "Default")
      (node (ref "J2") (pin "2") (pinfunction "2_2") (pintype "bidirectional"))
      (node (ref "TP_SWDIO") (pin "TP") (pinfunction "TP_TP") (pintype "input"))
      (node (ref "U1") (pin "P$AC24") (pinfunction "SWDIO_P$AC24") (pintype "bidirectional"))
    )
    (net (code "97") (name "SWO") (class "Default")
      (node (ref "TP_SWO") (pin "TP") (pinfunction "TP_TP") (pintype "input"))
      (node (ref "U1") (pin "P$AD22") (pinfunction "P1.00_P$AD22") (pintype "bidirectional"))
    )
    (net (code "98") (name "VBAT") (class "Default")
      (node (ref "C27") (pin "2") (pinfunction "2_2") (pintype "passive"))
      (node (ref "C37") (pin "2") (pinfunction "2_2") (pintype "passive"))
      (node (ref "IC1") (pin "C2") (pinfunction "BAT_C2") (pintype "bidirectional"))
      (node (ref "TP_VBAT") (pin "TP") (pinfunction "TP_TP") (pintype "input"))
      (node (ref "U3") (pin "2") (pinfunction "CELL_2") (pintype "power_in"))
      (node (ref "U3") (pin "3") (pinfunction "VDD_3") (pintype "power_in"))
    )
    (net (code "99") (name "VBUS") (class "Default")
      (node (ref "C21") (pin "1") (pinfunction "1_1") (pintype "passive"))
      (node (ref "C38") (pin "2") (pinfunction "2_2") (pintype "passive"))
      (node (ref "C42") (pin "1") (pinfunction "1_1") (pintype "passive"))
      (node (ref "C43") (pin "1") (pinfunction "1_1") (pintype "passive"))
      (node (ref "D3") (pin "5") (pinfunction "VBUS_5") (pintype "bidirectional"))
      (node (ref "IC1") (pin "A2") (pinfunction "IN_A2") (pintype "bidirectional"))
      (node (ref "J4") (pin "A4_B9") (pinfunction "VBUS_A4_B9") (pintype "power_in"))
      (node (ref "J4") (pin "A9_B4") (pinfunction "VBUS_A9_B4") (pintype "power_in"))
      (node (ref "U1") (pin "P$AD2") (pinfunction "VBUS_P$AD2") (pintype "power_in"))
    )
    (net (code "100") (name "VREG") (class "Default")
      (node (ref "C23") (pin "2") (pinfunction "2_2") (pintype "passive"))
      (node (ref "C24") (pin "2") (pinfunction "2_2") (pintype "passive"))
      (node (ref "C39") (pin "1") (pinfunction "1_1") (pintype "passive"))
      (node (ref "IC1") (pin "B2") (pinfunction "SYS_B2") (pintype "bidirectional"))
      (node (ref "IC9") (pin "A1") (pinfunction "EN_A1") (pintype "bidirectional"))
      (node (ref "IC9") (pin "A2") (pinfunction "VIN_1_A2") (pintype "bidirectional"))
      (node (ref "IC9") (pin "A3") (pinfunction "VIN_2_A3") (pintype "bidirectional"))
      (node (ref "TP_VREG") (pin "TP") (pinfunction "TP_TP") (pintype "input"))
    )
    (net (code "101") (name "unconnected-(ANT1-NC-Pad2)") (class "Default")
      (node (ref "ANT1") (pin "2") (pinfunction "NC_2") (pintype "no_connect"))
    )
    (net (code "102") (name "unconnected-(IC3-ASCL-Pad11)") (class "Default")
      (node (ref "IC3") (pin "11") (pinfunction "ASCL_11") (pintype "bidirectional"))
    )
    (net (code "103") (name "unconnected-(IC3-ASDA-Pad4)") (class "Default")
      (node (ref "IC3") (pin "4") (pinfunction "ASDA_4") (pintype "bidirectional"))
    )
    (net (code "104") (name "unconnected-(IC9-AGND-PadC1)") (class "Default")
      (node (ref "IC9") (pin "C1") (pinfunction "AGND_C1") (pintype "bidirectional"))
    )
    (net (code "105") (name "unconnected-(J1-Pad1)") (class "Default")
      (node (ref "J1") (pin "1") (pinfunction "1_1") (pintype "bidirectional"))
    )
    (net (code "106") (name "unconnected-(J1-Pad6)") (class "Default")
      (node (ref "J1") (pin "6") (pinfunction "6_6") (pintype "bidirectional"))
    )
    (net (code "107") (name "unconnected-(J1-Pad7)") (class "Default")
      (node (ref "J1") (pin "7") (pinfunction "7_7") (pintype "bidirectional"))
    )
    (net (code "108") (name "unconnected-(J4-SBU1-PadA8)") (class "Default")
      (node (ref "J4") (pin "A8") (pinfunction "SBU1_A8") (pintype "bidirectional"))
    )
    (net (code "109") (name "unconnected-(J4-SBU2-PadB8)") (class "Default")
      (node (ref "J4") (pin "B8") (pinfunction "SBU2_B8") (pintype "bidirectional"))
    )
    (net (code "110") (name "unconnected-(U1-DCCH-PadP$AB2)") (class "Default")
      (node (ref "U1") (pin "P$AB2") (pinfunction "DCCH_P$AB2") (pintype "bidirectional"))
    )
  )
)
